# streams_v05.net
KiCad netlist of a schematic drawn in EAGLE
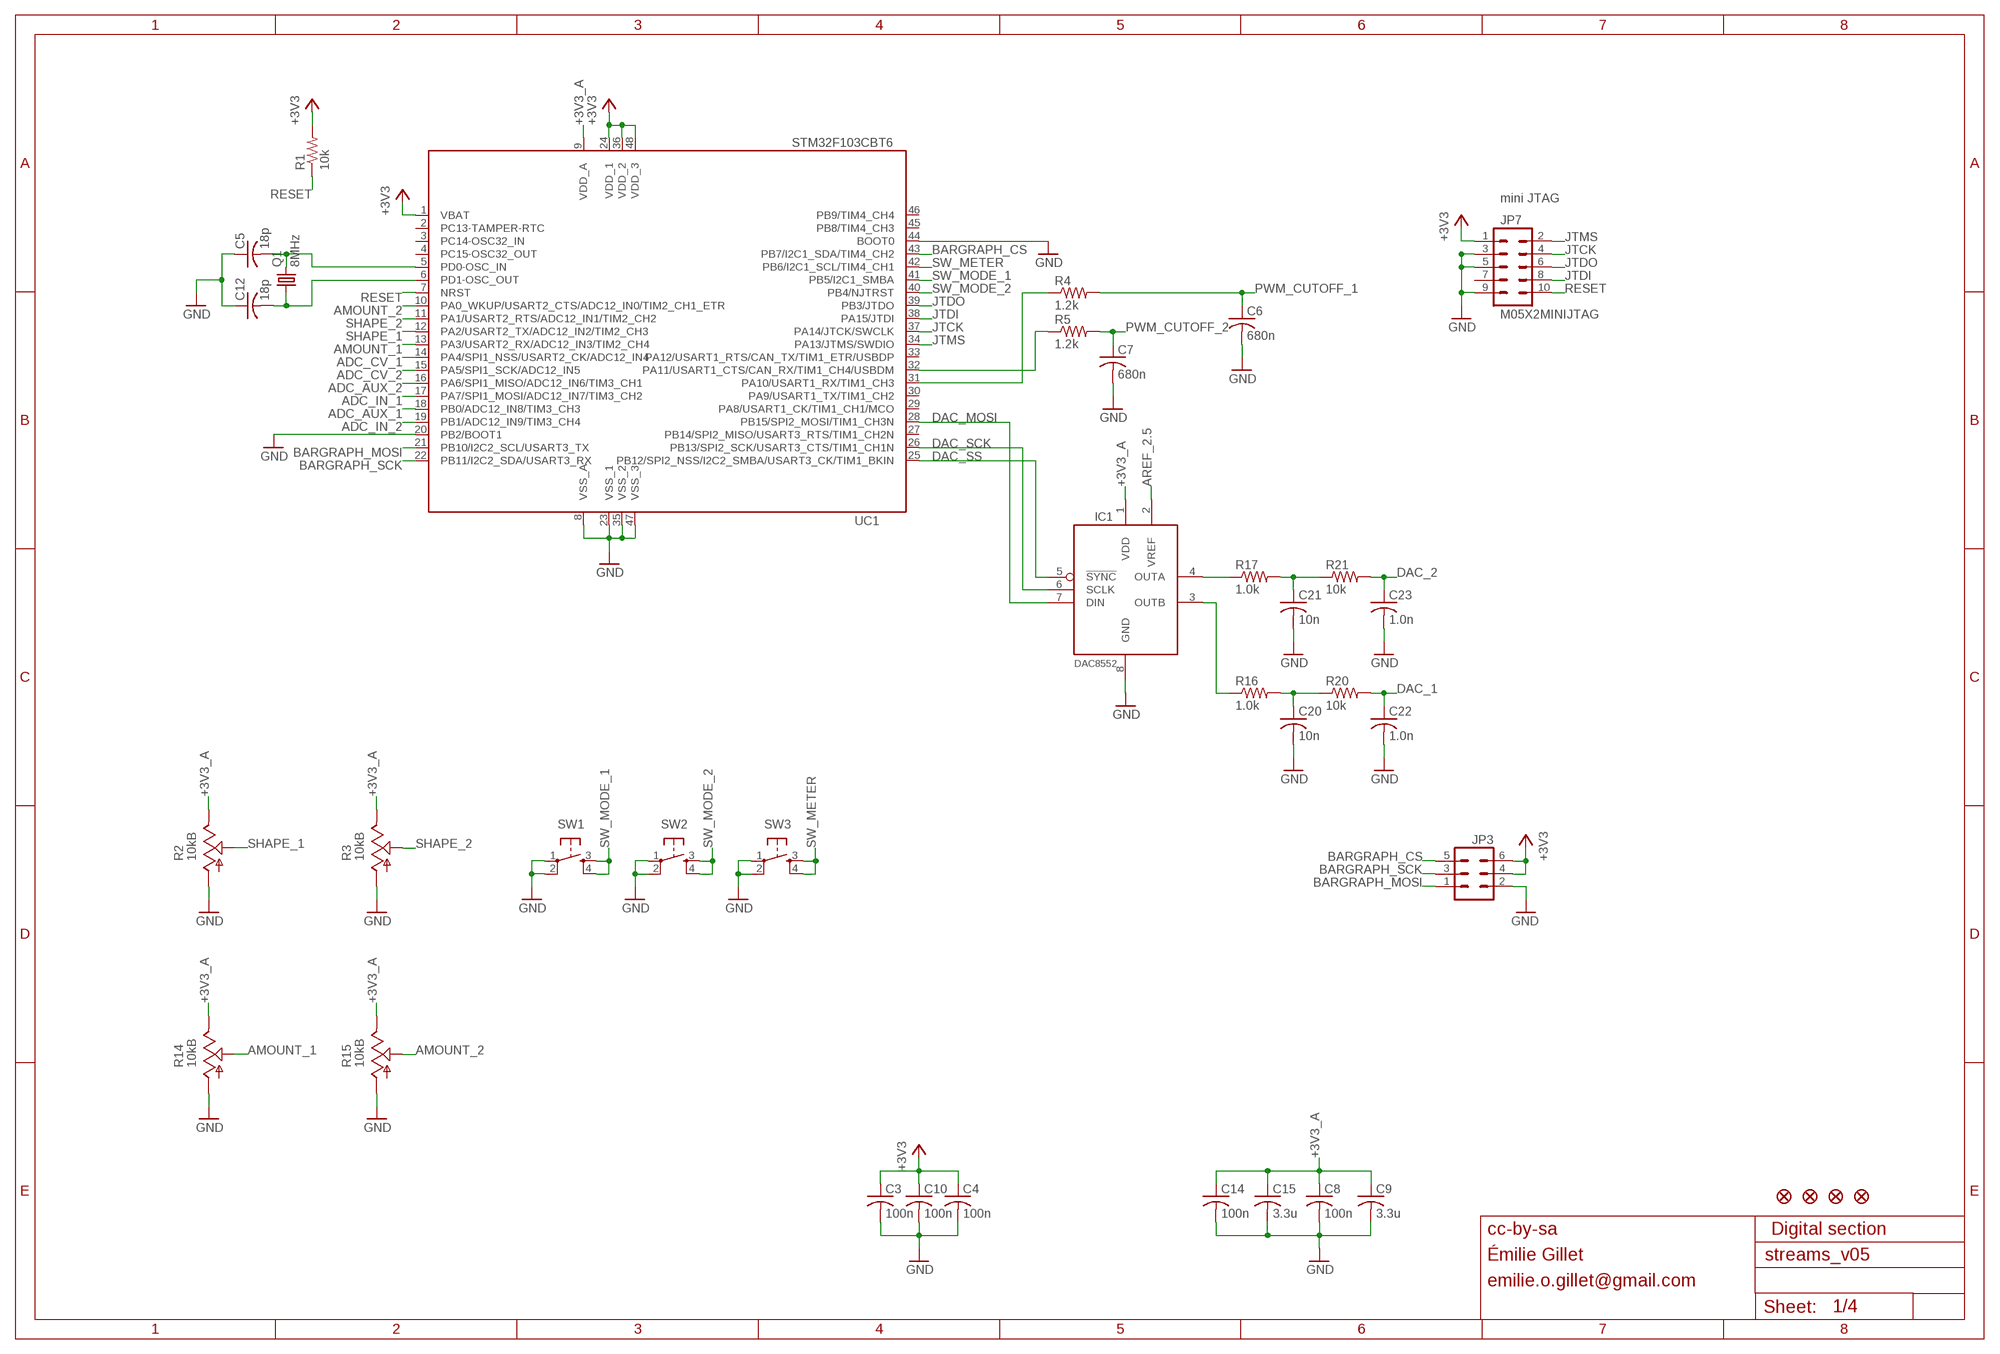
[diagram p0: schematic, sheet 1]
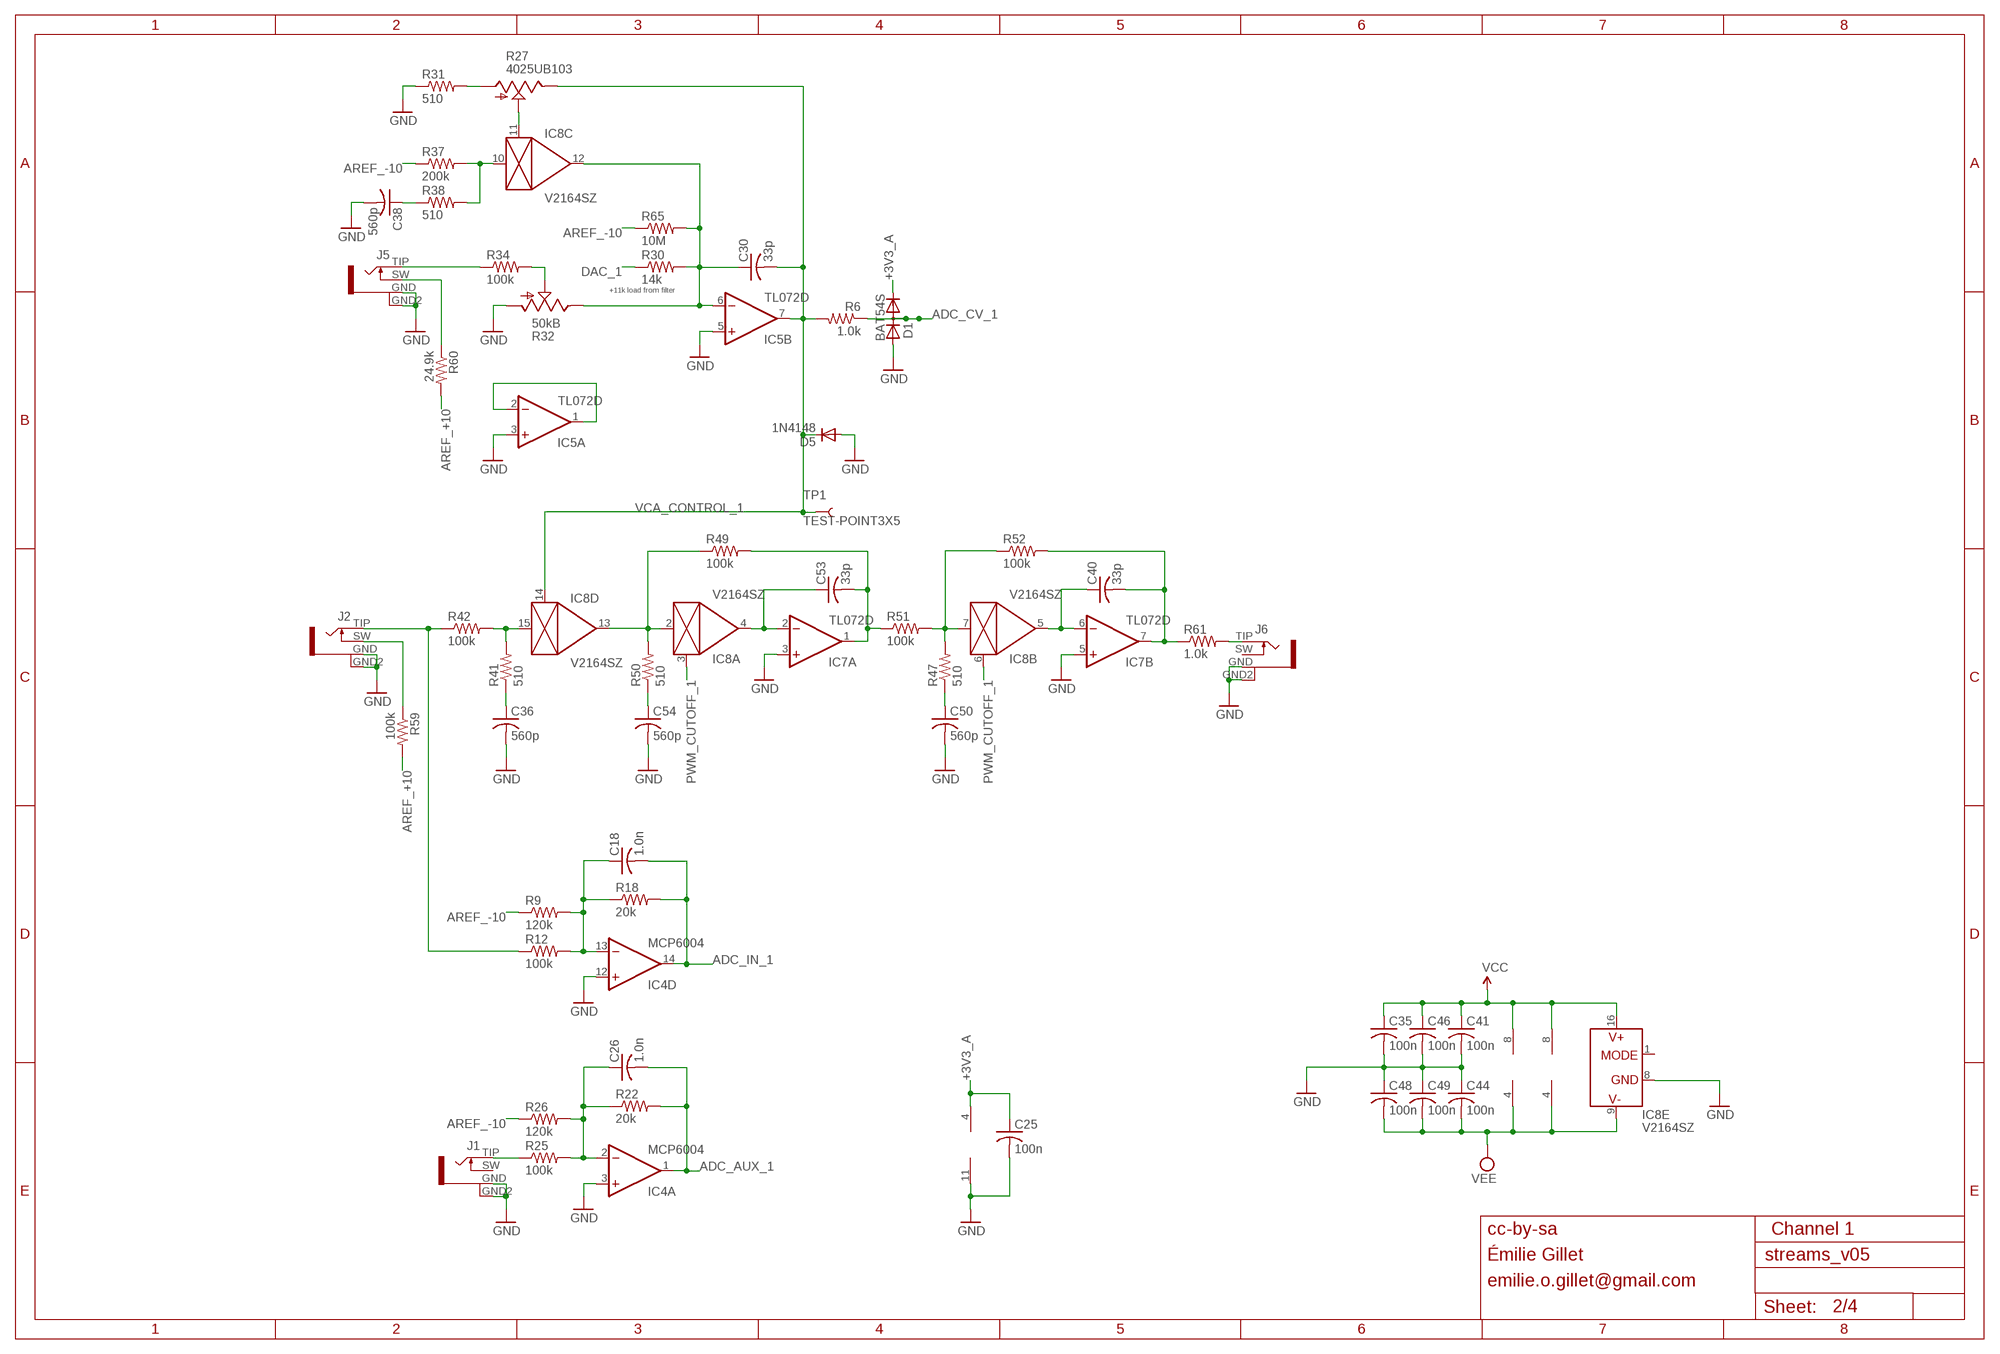
[diagram p1: schematic, sheet 2]
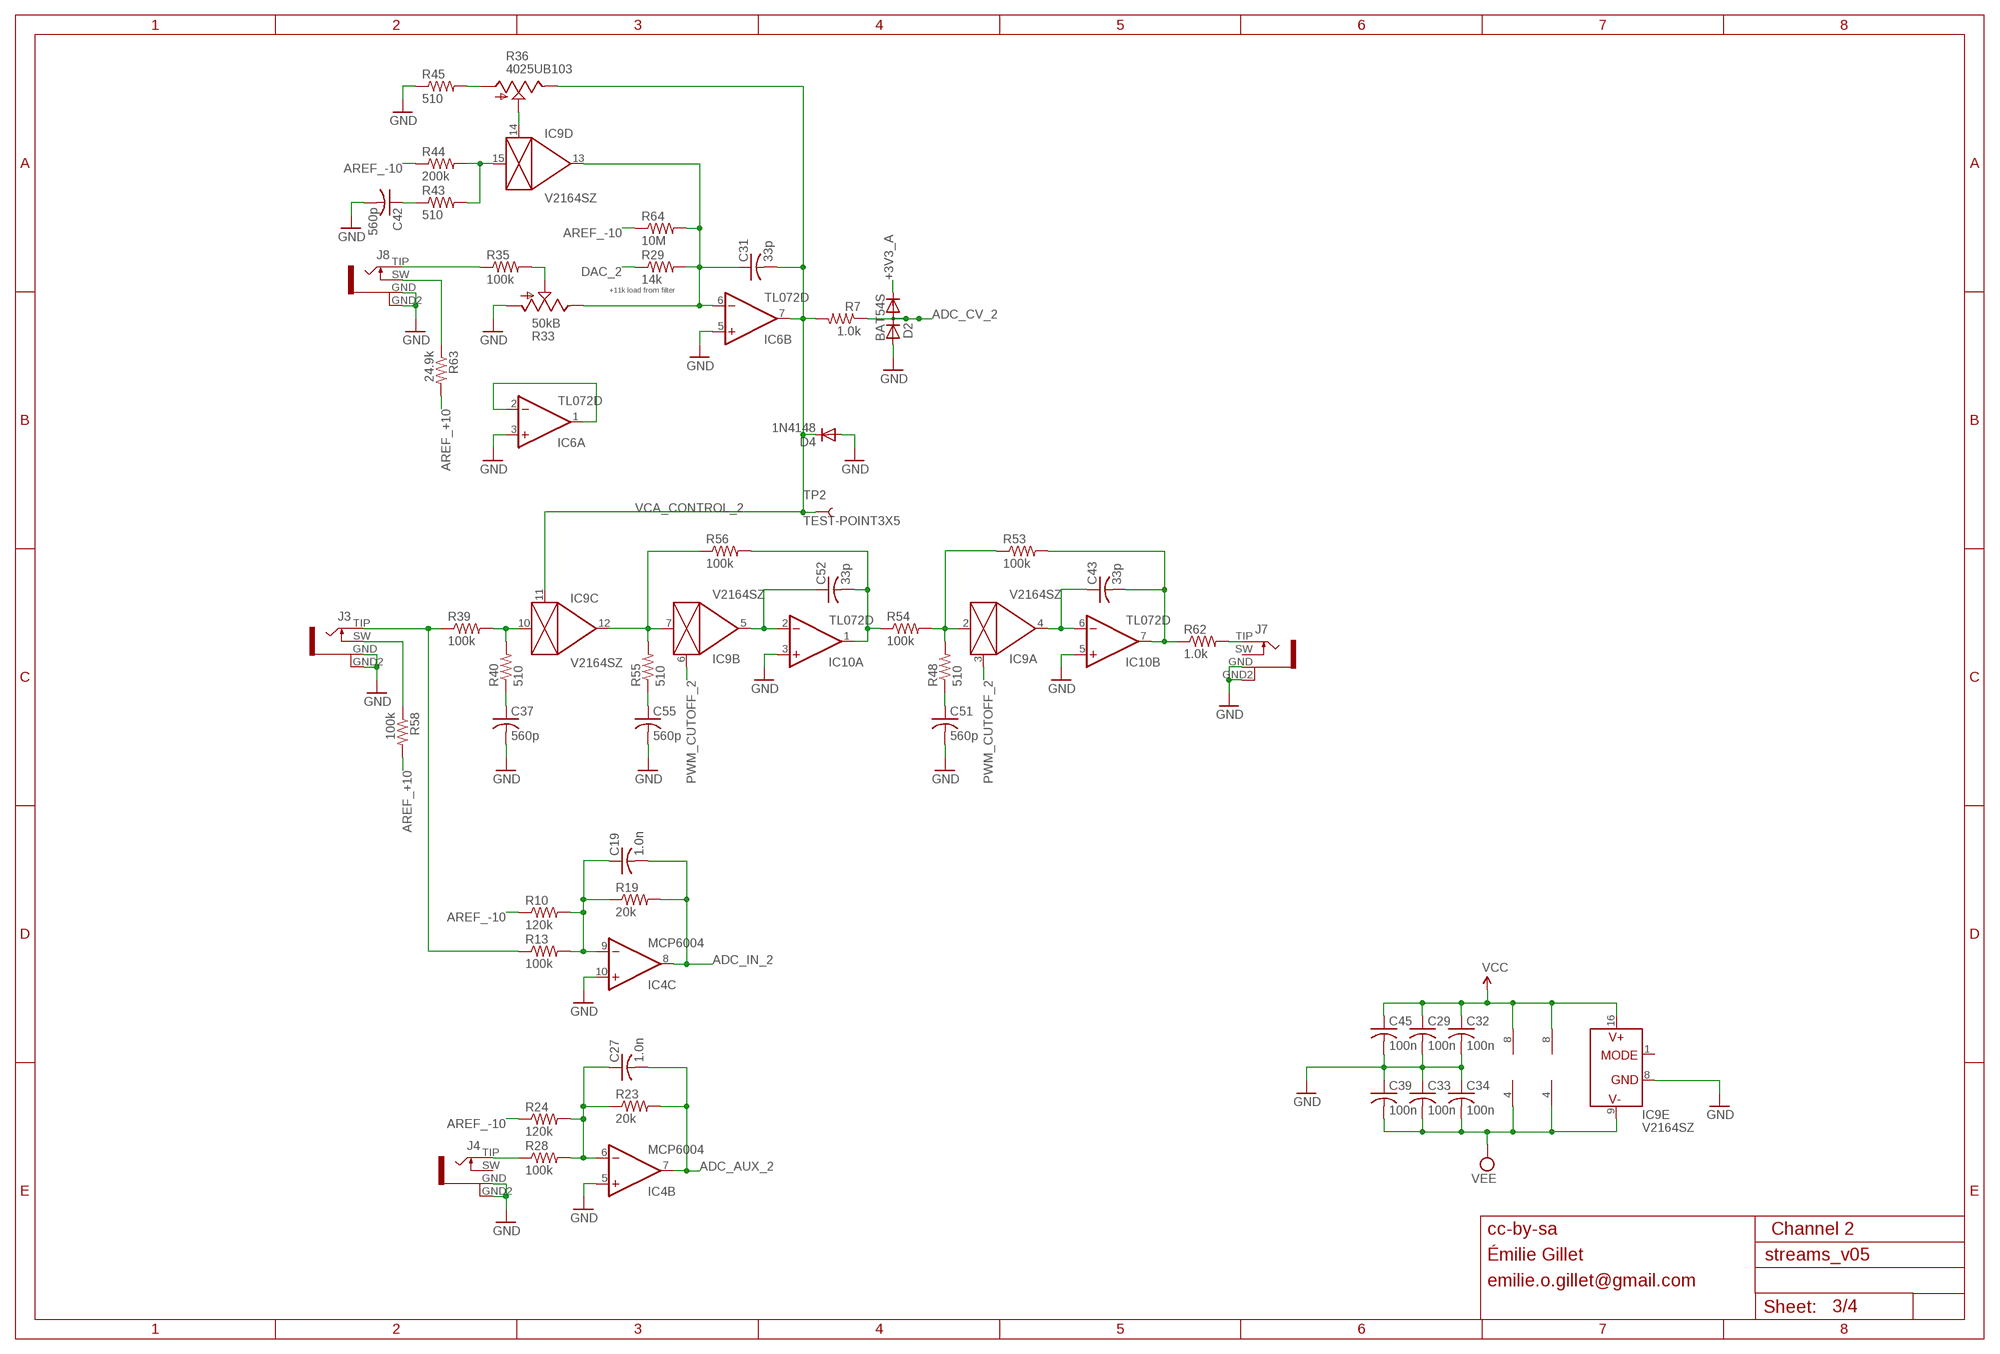
[diagram p2: schematic, sheet 3]
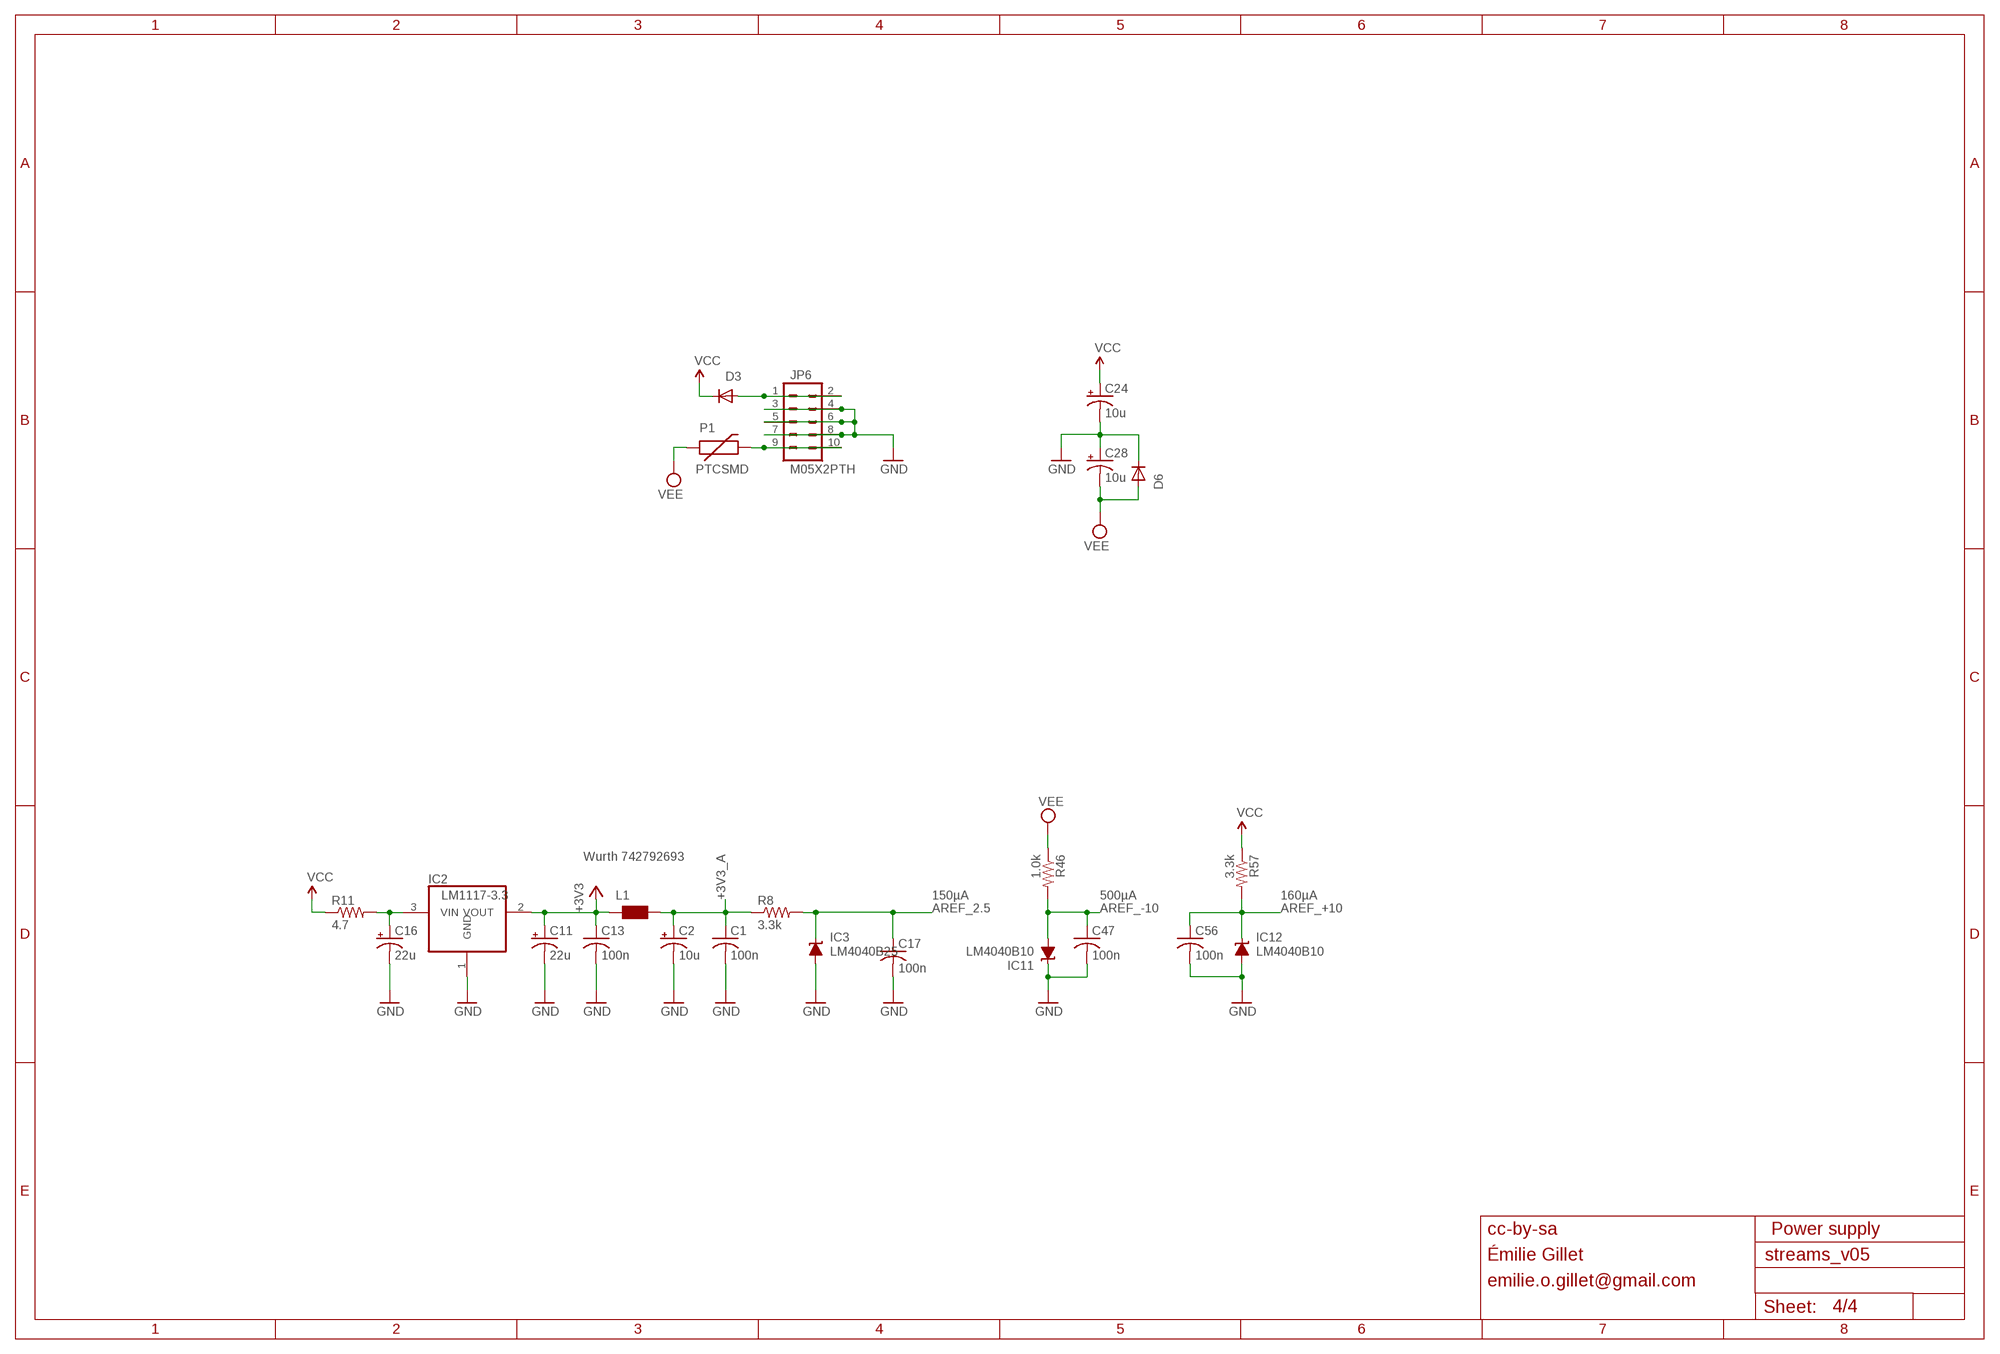
[diagram p3: schematic, sheet 4]

(export (version "E")
  (design (tool "Eeschema 10.0.6"))
  (components
    (comp (ref "C19")
      (value "1.0n")
      (footprint "eagle-import:C0603")
      (libsource (lib "eagle-import") (part "C-USC0603"))
    )
    (comp (ref "C27")
      (value "1.0n")
      (footprint "eagle-import:C0603")
      (libsource (lib "eagle-import") (part "C-USC0603"))
    )
    (comp (ref "C29")
      (value "100n")
      (footprint "eagle-import:C0603")
      (libsource (lib "eagle-import") (part "C-USC0603"))
    )
    (comp (ref "C31")
      (value "33p")
      (footprint "eagle-import:C0603")
      (libsource (lib "eagle-import") (part "C-USC0603"))
    )
    (comp (ref "C32")
      (value "100n")
      (footprint "eagle-import:C0603")
      (libsource (lib "eagle-import") (part "C-USC0603"))
    )
    (comp (ref "C33")
      (value "100n")
      (footprint "eagle-import:C0603")
      (libsource (lib "eagle-import") (part "C-USC0603"))
    )
    (comp (ref "C34")
      (value "100n")
      (footprint "eagle-import:C0603")
      (libsource (lib "eagle-import") (part "C-USC0603"))
    )
    (comp (ref "C37")
      (value "560p")
      (footprint "eagle-import:C0603")
      (libsource (lib "eagle-import") (part "C-USC0603"))
    )
    (comp (ref "C39")
      (value "100n")
      (footprint "eagle-import:C0603")
      (libsource (lib "eagle-import") (part "C-USC0603"))
    )
    (comp (ref "C42")
      (value "560p")
      (footprint "eagle-import:C0603")
      (libsource (lib "eagle-import") (part "C-USC0603"))
    )
    (comp (ref "C43")
      (value "33p")
      (footprint "eagle-import:C0603")
      (libsource (lib "eagle-import") (part "C-USC0603"))
    )
    (comp (ref "C45")
      (value "100n")
      (footprint "eagle-import:C0603")
      (libsource (lib "eagle-import") (part "C-USC0603"))
    )
    (comp (ref "C51")
      (value "560p")
      (footprint "eagle-import:C0603")
      (libsource (lib "eagle-import") (part "C-USC0603"))
    )
    (comp (ref "C52")
      (value "33p")
      (footprint "eagle-import:C0603")
      (libsource (lib "eagle-import") (part "C-USC0603"))
    )
    (comp (ref "C55")
      (value "560p")
      (footprint "eagle-import:C0603")
      (libsource (lib "eagle-import") (part "C-USC0603"))
    )
    (comp (ref "D2")
      (value "BAT54S")
      (footprint "eagle-import:SOT23")
      (libsource (lib "eagle-import") (part "DIODE_2CACA-SOT23"))
    )
    (comp (ref "D4")
      (value "1N4148")
      (footprint "eagle-import:SOD323-W")
      (libsource (lib "eagle-import") (part "DIODE-SOD323-W"))
    )
    (comp (ref "IC4")
      (value "MCP6004")
      (footprint "eagle-import:SO14")
      (libsource (lib "eagle-import") (part "TL074D"))
    )
    (comp (ref "IC6")
      (value "TL072D")
      (footprint "eagle-import:SO08")
      (libsource (lib "eagle-import") (part "TL072D"))
    )
    (comp (ref "IC9")
      (value "V2164SZ")
      (footprint "eagle-import:SOIC16N")
      (libsource (lib "eagle-import") (part "SSM2164S"))
    )
    (comp (ref "IC10")
      (value "TL072D")
      (footprint "eagle-import:SO08")
      (libsource (lib "eagle-import") (part "TL072D"))
    )
    (comp (ref "J3")
      (value "PJ301WQP")
      (footprint "eagle-import:WQP_PJ_301BM_WIDER")
      (libsource (lib "eagle-import") (part "PJ301WQP"))
    )
    (comp (ref "J4")
      (value "PJ301WQP")
      (footprint "eagle-import:WQP_PJ_301BM_WIDER")
      (libsource (lib "eagle-import") (part "PJ301WQP"))
    )
    (comp (ref "J7")
      (value "PJ301WQP")
      (footprint "eagle-import:WQP_PJ_301BM_WIDER")
      (libsource (lib "eagle-import") (part "PJ301WQP"))
    )
    (comp (ref "J8")
      (value "PJ301WQP")
      (footprint "eagle-import:WQP_PJ_301BM_WIDER")
      (libsource (lib "eagle-import") (part "PJ301WQP"))
    )
    (comp (ref "R7")
      (value "1.0k")
      (footprint "eagle-import:R0603")
      (libsource (lib "eagle-import") (part "R-US_R0603"))
    )
    (comp (ref "R10")
      (value "120k")
      (footprint "eagle-import:R0603")
      (libsource (lib "eagle-import") (part "R-US_R0603"))
    )
    (comp (ref "R13")
      (value "100k")
      (footprint "eagle-import:R0603")
      (libsource (lib "eagle-import") (part "R-US_R0603"))
    )
    (comp (ref "R19")
      (value "20k")
      (footprint "eagle-import:R0603")
      (libsource (lib "eagle-import") (part "R-US_R0603"))
    )
    (comp (ref "R23")
      (value "20k")
      (footprint "eagle-import:R0603")
      (libsource (lib "eagle-import") (part "R-US_R0603"))
    )
    (comp (ref "R24")
      (value "120k")
      (footprint "eagle-import:R0603")
      (libsource (lib "eagle-import") (part "R-US_R0603"))
    )
    (comp (ref "R28")
      (value "100k")
      (footprint "eagle-import:R0603")
      (libsource (lib "eagle-import") (part "R-US_R0603"))
    )
    (comp (ref "R29")
      (value "14k")
      (footprint "eagle-import:R0603")
      (libsource (lib "eagle-import") (part "R-US_R0603"))
    )
    (comp (ref "R33")
      (value "50kB")
      (footprint "eagle-import:ALPS_POT_VERTICAL_PS")
      (libsource (lib "eagle-import") (part "POT_USVERTICAL_PS"))
    )
    (comp (ref "R35")
      (value "100k")
      (footprint "eagle-import:R0603")
      (libsource (lib "eagle-import") (part "R-US_R0603"))
    )
    (comp (ref "R36")
      (value "4025UB103")
      (footprint "eagle-import:ALPS_POT_VERTICAL")
      (libsource (lib "eagle-import") (part "POT_USVERTICAL"))
    )
    (comp (ref "R39")
      (value "100k")
      (footprint "eagle-import:R0603")
      (libsource (lib "eagle-import") (part "R-US_R0603"))
    )
    (comp (ref "R40")
      (value "510")
      (footprint "eagle-import:R0603")
      (libsource (lib "eagle-import") (part "R-US_R0603"))
    )
    (comp (ref "R43")
      (value "510")
      (footprint "eagle-import:R0603")
      (libsource (lib "eagle-import") (part "R-US_R0603"))
    )
    (comp (ref "R44")
      (value "200k")
      (footprint "eagle-import:R0603")
      (libsource (lib "eagle-import") (part "R-US_R0603"))
    )
    (comp (ref "R45")
      (value "510")
      (footprint "eagle-import:R0603")
      (libsource (lib "eagle-import") (part "R-US_R0603"))
    )
    (comp (ref "R48")
      (value "510")
      (footprint "eagle-import:R0603")
      (libsource (lib "eagle-import") (part "R-US_R0603"))
    )
    (comp (ref "R53")
      (value "100k")
      (footprint "eagle-import:R0603")
      (libsource (lib "eagle-import") (part "R-US_R0603"))
    )
    (comp (ref "R54")
      (value "100k")
      (footprint "eagle-import:R0603")
      (libsource (lib "eagle-import") (part "R-US_R0603"))
    )
    (comp (ref "R55")
      (value "510")
      (footprint "eagle-import:R0603")
      (libsource (lib "eagle-import") (part "R-US_R0603"))
    )
    (comp (ref "R56")
      (value "100k")
      (footprint "eagle-import:R0603")
      (libsource (lib "eagle-import") (part "R-US_R0603"))
    )
    (comp (ref "R58")
      (value "100k")
      (footprint "eagle-import:R0603")
      (libsource (lib "eagle-import") (part "R-US_R0603"))
    )
    (comp (ref "R62")
      (value "1.0k")
      (footprint "eagle-import:R0603")
      (libsource (lib "eagle-import") (part "R-US_R0603"))
    )
    (comp (ref "R63")
      (value "24.9k")
      (footprint "eagle-import:R0603")
      (libsource (lib "eagle-import") (part "R-US_R0603"))
    )
    (comp (ref "R64")
      (value "10M")
      (footprint "eagle-import:R0603")
      (libsource (lib "eagle-import") (part "R-US_R0603"))
    )
    (comp (ref "TP2")
      (value "TEST-POINT3X5")
      (footprint "eagle-import:PAD.03X.05")
      (libsource (lib "eagle-import") (part "TEST-POINT3X5"))
    )
    (comp (ref "C18")
      (value "1.0n")
      (footprint "eagle-import:C0603")
      (libsource (lib "eagle-import") (part "C-USC0603"))
    )
    (comp (ref "C25")
      (value "100n")
      (footprint "eagle-import:C0603")
      (libsource (lib "eagle-import") (part "C-USC0603"))
    )
    (comp (ref "C26")
      (value "1.0n")
      (footprint "eagle-import:C0603")
      (libsource (lib "eagle-import") (part "C-USC0603"))
    )
    (comp (ref "C30")
      (value "33p")
      (footprint "eagle-import:C0603")
      (libsource (lib "eagle-import") (part "C-USC0603"))
    )
    (comp (ref "C35")
      (value "100n")
      (footprint "eagle-import:C0603")
      (libsource (lib "eagle-import") (part "C-USC0603"))
    )
    (comp (ref "C36")
      (value "560p")
      (footprint "eagle-import:C0603")
      (libsource (lib "eagle-import") (part "C-USC0603"))
    )
    (comp (ref "C38")
      (value "560p")
      (footprint "eagle-import:C0603")
      (libsource (lib "eagle-import") (part "C-USC0603"))
    )
    (comp (ref "C40")
      (value "33p")
      (footprint "eagle-import:C0603")
      (libsource (lib "eagle-import") (part "C-USC0603"))
    )
    (comp (ref "C41")
      (value "100n")
      (footprint "eagle-import:C0603")
      (libsource (lib "eagle-import") (part "C-USC0603"))
    )
    (comp (ref "C44")
      (value "100n")
      (footprint "eagle-import:C0603")
      (libsource (lib "eagle-import") (part "C-USC0603"))
    )
    (comp (ref "C46")
      (value "100n")
      (footprint "eagle-import:C0603")
      (libsource (lib "eagle-import") (part "C-USC0603"))
    )
    (comp (ref "C48")
      (value "100n")
      (footprint "eagle-import:C0603")
      (libsource (lib "eagle-import") (part "C-USC0603"))
    )
    (comp (ref "C49")
      (value "100n")
      (footprint "eagle-import:C0603")
      (libsource (lib "eagle-import") (part "C-USC0603"))
    )
    (comp (ref "C50")
      (value "560p")
      (footprint "eagle-import:C0603")
      (libsource (lib "eagle-import") (part "C-USC0603"))
    )
    (comp (ref "C53")
      (value "33p")
      (footprint "eagle-import:C0603")
      (libsource (lib "eagle-import") (part "C-USC0603"))
    )
    (comp (ref "C54")
      (value "560p")
      (footprint "eagle-import:C0603")
      (libsource (lib "eagle-import") (part "C-USC0603"))
    )
    (comp (ref "D1")
      (value "BAT54S")
      (footprint "eagle-import:SOT23")
      (libsource (lib "eagle-import") (part "DIODE_2CACA-SOT23"))
    )
    (comp (ref "D5")
      (value "1N4148")
      (footprint "eagle-import:SOD323-W")
      (libsource (lib "eagle-import") (part "DIODE-SOD323-W"))
    )
    (comp (ref "IC5")
      (value "TL072D")
      (footprint "eagle-import:SO08")
      (libsource (lib "eagle-import") (part "TL072D"))
    )
    (comp (ref "IC7")
      (value "TL072D")
      (footprint "eagle-import:SO08")
      (libsource (lib "eagle-import") (part "TL072D"))
    )
    (comp (ref "IC8")
      (value "V2164SZ")
      (footprint "eagle-import:SOIC16N")
      (libsource (lib "eagle-import") (part "SSM2164S"))
    )
    (comp (ref "J1")
      (value "PJ301WQP")
      (footprint "eagle-import:WQP_PJ_301BM_WIDER")
      (libsource (lib "eagle-import") (part "PJ301WQP"))
    )
    (comp (ref "J2")
      (value "PJ301WQP")
      (footprint "eagle-import:WQP_PJ_301BM_WIDER")
      (libsource (lib "eagle-import") (part "PJ301WQP"))
    )
    (comp (ref "J5")
      (value "PJ301WQP")
      (footprint "eagle-import:WQP_PJ_301BM_WIDER")
      (libsource (lib "eagle-import") (part "PJ301WQP"))
    )
    (comp (ref "J6")
      (value "PJ301WQP")
      (footprint "eagle-import:WQP_PJ_301BM_WIDER")
      (libsource (lib "eagle-import") (part "PJ301WQP"))
    )
    (comp (ref "R6")
      (value "1.0k")
      (footprint "eagle-import:R0603")
      (libsource (lib "eagle-import") (part "R-US_R0603"))
    )
    (comp (ref "R9")
      (value "120k")
      (footprint "eagle-import:R0603")
      (libsource (lib "eagle-import") (part "R-US_R0603"))
    )
    (comp (ref "R12")
      (value "100k")
      (footprint "eagle-import:R0603")
      (libsource (lib "eagle-import") (part "R-US_R0603"))
    )
    (comp (ref "R18")
      (value "20k")
      (footprint "eagle-import:R0603")
      (libsource (lib "eagle-import") (part "R-US_R0603"))
    )
    (comp (ref "R22")
      (value "20k")
      (footprint "eagle-import:R0603")
      (libsource (lib "eagle-import") (part "R-US_R0603"))
    )
    (comp (ref "R25")
      (value "100k")
      (footprint "eagle-import:R0603")
      (libsource (lib "eagle-import") (part "R-US_R0603"))
    )
    (comp (ref "R26")
      (value "120k")
      (footprint "eagle-import:R0603")
      (libsource (lib "eagle-import") (part "R-US_R0603"))
    )
    (comp (ref "R27")
      (value "4025UB103")
      (footprint "eagle-import:ALPS_POT_VERTICAL")
      (libsource (lib "eagle-import") (part "POT_USVERTICAL"))
    )
    (comp (ref "R30")
      (value "14k")
      (footprint "eagle-import:R0603")
      (libsource (lib "eagle-import") (part "R-US_R0603"))
    )
    (comp (ref "R31")
      (value "510")
      (footprint "eagle-import:R0603")
      (libsource (lib "eagle-import") (part "R-US_R0603"))
    )
    (comp (ref "R32")
      (value "50kB")
      (footprint "eagle-import:ALPS_POT_VERTICAL_PS")
      (libsource (lib "eagle-import") (part "POT_USVERTICAL_PS"))
    )
    (comp (ref "R34")
      (value "100k")
      (footprint "eagle-import:R0603")
      (libsource (lib "eagle-import") (part "R-US_R0603"))
    )
    (comp (ref "R37")
      (value "200k")
      (footprint "eagle-import:R0603")
      (libsource (lib "eagle-import") (part "R-US_R0603"))
    )
    (comp (ref "R38")
      (value "510")
      (footprint "eagle-import:R0603")
      (libsource (lib "eagle-import") (part "R-US_R0603"))
    )
    (comp (ref "R41")
      (value "510")
      (footprint "eagle-import:R0603")
      (libsource (lib "eagle-import") (part "R-US_R0603"))
    )
    (comp (ref "R42")
      (value "100k")
      (footprint "eagle-import:R0603")
      (libsource (lib "eagle-import") (part "R-US_R0603"))
    )
    (comp (ref "R47")
      (value "510")
      (footprint "eagle-import:R0603")
      (libsource (lib "eagle-import") (part "R-US_R0603"))
    )
    (comp (ref "R49")
      (value "100k")
      (footprint "eagle-import:R0603")
      (libsource (lib "eagle-import") (part "R-US_R0603"))
    )
    (comp (ref "R50")
      (value "510")
      (footprint "eagle-import:R0603")
      (libsource (lib "eagle-import") (part "R-US_R0603"))
    )
    (comp (ref "R51")
      (value "100k")
      (footprint "eagle-import:R0603")
      (libsource (lib "eagle-import") (part "R-US_R0603"))
    )
    (comp (ref "R52")
      (value "100k")
      (footprint "eagle-import:R0603")
      (libsource (lib "eagle-import") (part "R-US_R0603"))
    )
    (comp (ref "R59")
      (value "100k")
      (footprint "eagle-import:R0603")
      (libsource (lib "eagle-import") (part "R-US_R0603"))
    )
    (comp (ref "R60")
      (value "24.9k")
      (footprint "eagle-import:R0603")
      (libsource (lib "eagle-import") (part "R-US_R0603"))
    )
    (comp (ref "R61")
      (value "1.0k")
      (footprint "eagle-import:R0603")
      (libsource (lib "eagle-import") (part "R-US_R0603"))
    )
    (comp (ref "R65")
      (value "10M")
      (footprint "eagle-import:R0603")
      (libsource (lib "eagle-import") (part "R-US_R0603"))
    )
    (comp (ref "TP1")
      (value "TEST-POINT3X5")
      (footprint "eagle-import:PAD.03X.05")
      (libsource (lib "eagle-import") (part "TEST-POINT3X5"))
    )
    (comp (ref "C1")
      (value "100n")
      (footprint "eagle-import:C0603")
      (libsource (lib "eagle-import") (part "C-USC0603"))
    )
    (comp (ref "C2")
      (value "10u")
      (footprint "eagle-import:PANASONIC_B")
      (libsource (lib "eagle-import") (part "CPOL-USB"))
    )
    (comp (ref "C11")
      (value "22u")
      (footprint "eagle-import:PANASONIC_B")
      (libsource (lib "eagle-import") (part "CPOL-USB"))
    )
    (comp (ref "C13")
      (value "100n")
      (footprint "eagle-import:C0603")
      (libsource (lib "eagle-import") (part "C-USC0603"))
    )
    (comp (ref "C16")
      (value "22u")
      (footprint "eagle-import:PANASONIC_C")
      (libsource (lib "eagle-import") (part "CPOL-USC"))
    )
    (comp (ref "C17")
      (value "100n")
      (footprint "eagle-import:C0603")
      (libsource (lib "eagle-import") (part "C-USC0603"))
    )
    (comp (ref "C24")
      (value "10u")
      (footprint "eagle-import:PANASONIC_B")
      (libsource (lib "eagle-import") (part "CPOL-USB"))
    )
    (comp (ref "C28")
      (value "10u")
      (footprint "eagle-import:PANASONIC_B")
      (libsource (lib "eagle-import") (part "CPOL-USB"))
    )
    (comp (ref "C47")
      (value "100n")
      (footprint "eagle-import:C0603")
      (libsource (lib "eagle-import") (part "C-USC0603"))
    )
    (comp (ref "C56")
      (value "100n")
      (footprint "eagle-import:C0603")
      (libsource (lib "eagle-import") (part "C-USC0603"))
    )
    (comp (ref "D3")
      (value "1N5819HW")
      (footprint "eagle-import:SOD123")
      (libsource (lib "eagle-import") (part "DIODE-SOD123"))
    )
    (comp (ref "D6")
      (value "1N5819HW")
      (footprint "eagle-import:SOD123")
      (libsource (lib "eagle-import") (part "DIODE-SOD123"))
    )
    (comp (ref "IC2")
      (value "LM1117-3.3")
      (footprint "eagle-import:SOT223")
      (libsource (lib "eagle-import") (part "REG1117"))
    )
    (comp (ref "IC3")
      (value "LM4040B25")
      (footprint "eagle-import:DBZ_R-PDSO-G3")
      (libsource (lib "eagle-import") (part "LM4041DBZB12"))
    )
    (comp (ref "IC11")
      (value "LM4040B10")
      (footprint "eagle-import:DBZ_R-PDSO-G3")
      (libsource (lib "eagle-import") (part "LM4041DBZB12"))
    )
    (comp (ref "IC12")
      (value "LM4040B10")
      (footprint "eagle-import:DBZ_R-PDSO-G3")
      (libsource (lib "eagle-import") (part "LM4041DBZB12"))
    )
    (comp (ref "JP6")
      (value "M05X2PTH")
      (footprint "eagle-import:AVR_ICSP")
      (libsource (lib "eagle-import") (part "M05X2PTH"))
    )
    (comp (ref "L1")
      (value "WE-CBF_0603")
      (footprint "eagle-import:0603")
      (libsource (lib "eagle-import") (part "WE-CBF_0603"))
    )
    (comp (ref "P1")
      (value "PTCSMD")
      (footprint "eagle-import:PTC-1206")
      (libsource (lib "eagle-import") (part "PTCSMD"))
    )
    (comp (ref "R8")
      (value "3.3k")
      (footprint "eagle-import:R0603")
      (libsource (lib "eagle-import") (part "R-US_R0603"))
    )
    (comp (ref "R11")
      (value "4.7")
      (footprint "eagle-import:R1206")
      (libsource (lib "eagle-import") (part "R-US_R1206"))
    )
    (comp (ref "R46")
      (value "1.0k")
      (footprint "eagle-import:R0603")
      (libsource (lib "eagle-import") (part "R-US_R0603"))
    )
    (comp (ref "R57")
      (value "3.3k")
      (footprint "eagle-import:R0603")
      (libsource (lib "eagle-import") (part "R-US_R0603"))
    )
    (comp (ref "C3")
      (value "100n")
      (footprint "eagle-import:C0603")
      (libsource (lib "eagle-import") (part "C-USC0603"))
    )
    (comp (ref "C4")
      (value "100n")
      (footprint "eagle-import:C0603")
      (libsource (lib "eagle-import") (part "C-USC0603"))
    )
    (comp (ref "C5")
      (value "18p")
      (footprint "eagle-import:C0603")
      (libsource (lib "eagle-import") (part "C-USC0603"))
    )
    (comp (ref "C6")
      (value "680n")
      (footprint "eagle-import:C0603")
      (libsource (lib "eagle-import") (part "C-USC0603"))
    )
    (comp (ref "C7")
      (value "680n")
      (footprint "eagle-import:C0603")
      (libsource (lib "eagle-import") (part "C-USC0603"))
    )
    (comp (ref "C8")
      (value "100n")
      (footprint "eagle-import:C0603")
      (libsource (lib "eagle-import") (part "C-USC0603"))
    )
    (comp (ref "C9")
      (value "3.3u")
      (footprint "eagle-import:C0603")
      (libsource (lib "eagle-import") (part "C-USC0603"))
    )
    (comp (ref "C10")
      (value "100n")
      (footprint "eagle-import:C0603")
      (libsource (lib "eagle-import") (part "C-USC0603"))
    )
    (comp (ref "C12")
      (value "18p")
      (footprint "eagle-import:C0603")
      (libsource (lib "eagle-import") (part "C-USC0603"))
    )
    (comp (ref "C14")
      (value "100n")
      (footprint "eagle-import:C0603")
      (libsource (lib "eagle-import") (part "C-USC0603"))
    )
    (comp (ref "C15")
      (value "3.3u")
      (footprint "eagle-import:C0603")
      (libsource (lib "eagle-import") (part "C-USC0603"))
    )
    (comp (ref "C20")
      (value "10n")
      (footprint "eagle-import:C0603")
      (libsource (lib "eagle-import") (part "C-USC0603"))
    )
    (comp (ref "C21")
      (value "10n")
      (footprint "eagle-import:C0603")
      (libsource (lib "eagle-import") (part "C-USC0603"))
    )
    (comp (ref "C22")
      (value "1.0n")
      (footprint "eagle-import:C0603")
      (libsource (lib "eagle-import") (part "C-USC0603"))
    )
    (comp (ref "C23")
      (value "1.0n")
      (footprint "eagle-import:C0603")
      (libsource (lib "eagle-import") (part "C-USC0603"))
    )
    (comp (ref "IC1")
      (value "DAC8552")
      (footprint "eagle-import:MSOP-8")
      (libsource (lib "eagle-import") (part "DAC8552"))
    )
    (comp (ref "JP1")
      (value "FIDUCIAL1X2")
      (footprint "eagle-import:FIDUCIAL-1X2")
      (libsource (lib "eagle-import") (part "FIDUCIAL1X2"))
    )
    (comp (ref "JP2")
      (value "FIDUCIAL1X2")
      (footprint "eagle-import:FIDUCIAL-1X2")
      (libsource (lib "eagle-import") (part "FIDUCIAL1X2"))
    )
    (comp (ref "JP3")
      (value "M03X2BOTTOM")
      (footprint "eagle-import:2X3_BOTTOM")
      (libsource (lib "eagle-import") (part "M03X2BOTTOM"))
    )
    (comp (ref "JP4")
      (value "FIDUCIAL1X2")
      (footprint "eagle-import:FIDUCIAL-1X2")
      (libsource (lib "eagle-import") (part "FIDUCIAL1X2"))
    )
    (comp (ref "JP5")
      (value "FIDUCIAL1X2")
      (footprint "eagle-import:FIDUCIAL-1X2")
      (libsource (lib "eagle-import") (part "FIDUCIAL1X2"))
    )
    (comp (ref "JP7")
      (value "M05X2MINIJTAG")
      (footprint "eagle-import:2X5-1.27")
      (libsource (lib "eagle-import") (part "M05X2MINIJTAG"))
    )
    (comp (ref "Q1")
      (value "8MHz")
      (footprint "eagle-import:HC49UP")
      (libsource (lib "eagle-import") (part "CRYSTALHC49UP"))
    )
    (comp (ref "R1")
      (value "10k")
      (footprint "eagle-import:R0603")
      (libsource (lib "eagle-import") (part "R-US_R0603"))
    )
    (comp (ref "R2")
      (value "10kB")
      (footprint "eagle-import:ALPS_POT_VERTICAL_PS")
      (libsource (lib "eagle-import") (part "POT_USVERTICAL_PS"))
    )
    (comp (ref "R3")
      (value "10kB")
      (footprint "eagle-import:ALPS_POT_VERTICAL_PS")
      (libsource (lib "eagle-import") (part "POT_USVERTICAL_PS"))
    )
    (comp (ref "R4")
      (value "1.2k")
      (footprint "eagle-import:R0603")
      (libsource (lib "eagle-import") (part "R-US_R0603"))
    )
    (comp (ref "R5")
      (value "1.2k")
      (footprint "eagle-import:R0603")
      (libsource (lib "eagle-import") (part "R-US_R0603"))
    )
    (comp (ref "R14")
      (value "10kB")
      (footprint "eagle-import:ALPS_POT_VERTICAL_PS")
      (libsource (lib "eagle-import") (part "POT_USVERTICAL_PS"))
    )
    (comp (ref "R15")
      (value "10kB")
      (footprint "eagle-import:ALPS_POT_VERTICAL_PS")
      (libsource (lib "eagle-import") (part "POT_USVERTICAL_PS"))
    )
    (comp (ref "R16")
      (value "1.0k")
      (footprint "eagle-import:R0603")
      (libsource (lib "eagle-import") (part "R-US_R0603"))
    )
    (comp (ref "R17")
      (value "1.0k")
      (footprint "eagle-import:R0603")
      (libsource (lib "eagle-import") (part "R-US_R0603"))
    )
    (comp (ref "R20")
      (value "10k")
      (footprint "eagle-import:R0603")
      (libsource (lib "eagle-import") (part "R-US_R0603"))
    )
    (comp (ref "R21")
      (value "10k")
      (footprint "eagle-import:R0603")
      (libsource (lib "eagle-import") (part "R-US_R0603"))
    )
    (comp (ref "SW1")
      (value "TAC_SWITCHPTH")
      (footprint "eagle-import:TACTILE-PTH")
      (libsource (lib "eagle-import") (part "TAC_SWITCHPTH"))
    )
    (comp (ref "SW2")
      (value "TAC_SWITCHPTH")
      (footprint "eagle-import:TACTILE-PTH")
      (libsource (lib "eagle-import") (part "TAC_SWITCHPTH"))
    )
    (comp (ref "SW3")
      (value "TAC_SWITCHPTH")
      (footprint "eagle-import:TACTILE-PTH")
      (libsource (lib "eagle-import") (part "TAC_SWITCHPTH"))
    )
    (comp (ref "UC1")
      (value "STM32F103CBT6")
      (footprint "eagle-import:LQFP48")
      (libsource (lib "eagle-import") (part "STM32F103CB"))
    )
  )
  (nets
    (net (code "1") (name "+3V3") (class "Default")
      (node (ref "C10") (pin "1") (pinfunction "1_1") (pintype "passive"))
      (node (ref "C11") (pin "+") (pinfunction "+_+") (pintype "passive"))
      (node (ref "C13") (pin "1") (pinfunction "1_1") (pintype "passive"))
      (node (ref "C3") (pin "1") (pinfunction "1_1") (pintype "passive"))
      (node (ref "C4") (pin "1") (pinfunction "1_1") (pintype "passive"))
      (node (ref "IC2") (pin "2") (pinfunction "VOUT_2") (pintype "output"))
      (node (ref "JP3") (pin "4") (pinfunction "4_4") (pintype "passive"))
      (node (ref "JP3") (pin "6") (pinfunction "6_6") (pintype "passive"))
      (node (ref "JP7") (pin "1") (pinfunction "1_1") (pintype "passive"))
      (node (ref "L1") (pin "1") (pinfunction "1_1") (pintype "passive"))
      (node (ref "R1") (pin "2") (pinfunction "2_2") (pintype "passive"))
      (node (ref "UC1") (pin "1") (pinfunction "VBAT_1") (pintype "power_in"))
      (node (ref "UC1") (pin "24") (pinfunction "VDD_1_24") (pintype "power_in"))
      (node (ref "UC1") (pin "36") (pinfunction "VDD_2_36") (pintype "power_in"))
      (node (ref "UC1") (pin "48") (pinfunction "VDD_3_48") (pintype "power_in"))
    )
    (net (code "2") (name "+3V3_A") (class "Default")
      (node (ref "C1") (pin "1") (pinfunction "1_1") (pintype "passive"))
      (node (ref "C14") (pin "1") (pinfunction "1_1") (pintype "passive"))
      (node (ref "C15") (pin "1") (pinfunction "1_1") (pintype "passive"))
      (node (ref "C2") (pin "+") (pinfunction "+_+") (pintype "passive"))
      (node (ref "C25") (pin "1") (pinfunction "1_1") (pintype "passive"))
      (node (ref "C8") (pin "1") (pinfunction "1_1") (pintype "passive"))
      (node (ref "C9") (pin "1") (pinfunction "1_1") (pintype "passive"))
      (node (ref "D1") (pin "2") (pinfunction "C_2") (pintype "passive"))
      (node (ref "D2") (pin "2") (pinfunction "C_2") (pintype "passive"))
      (node (ref "IC1") (pin "1") (pinfunction "VDD_1") (pintype "power_in"))
      (node (ref "IC4") (pin "4") (pinfunction "V+_4") (pintype "power_in"))
      (node (ref "L1") (pin "2") (pinfunction "2_2") (pintype "passive"))
      (node (ref "R14") (pin "P$1") (pinfunction "E_P$1") (pintype "passive"))
      (node (ref "R15") (pin "P$1") (pinfunction "E_P$1") (pintype "passive"))
      (node (ref "R2") (pin "P$1") (pinfunction "E_P$1") (pintype "passive"))
      (node (ref "R3") (pin "P$1") (pinfunction "E_P$1") (pintype "passive"))
      (node (ref "R8") (pin "1") (pinfunction "1_1") (pintype "passive"))
      (node (ref "UC1") (pin "9") (pinfunction "VDD_A_9") (pintype "power_in"))
    )
    (net (code "3") (name "ADC_AUX_1") (class "Default")
      (node (ref "C26") (pin "2") (pinfunction "2_2") (pintype "passive"))
      (node (ref "IC4") (pin "1") (pinfunction "OUT_1") (pintype "output"))
      (node (ref "R22") (pin "2") (pinfunction "2_2") (pintype "passive"))
      (node (ref "UC1") (pin "18") (pinfunction "PB0/ADC12_IN8/TIM3_CH3_18") (pintype "bidirectional"))
    )
    (net (code "4") (name "ADC_AUX_2") (class "Default")
      (node (ref "C27") (pin "2") (pinfunction "2_2") (pintype "passive"))
      (node (ref "IC4") (pin "7") (pinfunction "OUT_7") (pintype "output"))
      (node (ref "R23") (pin "2") (pinfunction "2_2") (pintype "passive"))
      (node (ref "UC1") (pin "16") (pinfunction "PA6/SPI1_MISO/ADC12_IN6/TIM3_CH1_16") (pintype "bidirectional"))
    )
    (net (code "5") (name "ADC_CV_1") (class "Default")
      (node (ref "D1") (pin "3") (pinfunction "AC_3") (pintype "passive"))
      (node (ref "R6") (pin "1") (pinfunction "1_1") (pintype "passive"))
      (node (ref "UC1") (pin "14") (pinfunction "PA4/SPI1_NSS/USART2_CK/ADC12_IN4_14") (pintype "bidirectional"))
    )
    (net (code "6") (name "ADC_CV_2") (class "Default")
      (node (ref "D2") (pin "3") (pinfunction "AC_3") (pintype "passive"))
      (node (ref "R7") (pin "1") (pinfunction "1_1") (pintype "passive"))
      (node (ref "UC1") (pin "15") (pinfunction "PA5/SPI1_SCK/ADC12_IN5_15") (pintype "bidirectional"))
    )
    (net (code "7") (name "ADC_IN_1") (class "Default")
      (node (ref "C18") (pin "2") (pinfunction "2_2") (pintype "passive"))
      (node (ref "IC4") (pin "14") (pinfunction "OUT_14") (pintype "output"))
      (node (ref "R18") (pin "2") (pinfunction "2_2") (pintype "passive"))
      (node (ref "UC1") (pin "17") (pinfunction "PA7/SPI1_MOSI/ADC12_IN7/TIM3_CH2_17") (pintype "bidirectional"))
    )
    (net (code "8") (name "ADC_IN_2") (class "Default")
      (node (ref "C19") (pin "2") (pinfunction "2_2") (pintype "passive"))
      (node (ref "IC4") (pin "8") (pinfunction "OUT_8") (pintype "output"))
      (node (ref "R19") (pin "2") (pinfunction "2_2") (pintype "passive"))
      (node (ref "UC1") (pin "19") (pinfunction "PB1/ADC12_IN9/TIM3_CH4_19") (pintype "bidirectional"))
    )
    (net (code "9") (name "AMOUNT_1") (class "Default")
      (node (ref "R14") (pin "P$2") (pinfunction "S_P$2") (pintype "passive"))
      (node (ref "UC1") (pin "13") (pinfunction "PA3/USART2_RX/ADC12_IN3/TIM2_CH4_13") (pintype "bidirectional"))
    )
    (net (code "10") (name "AMOUNT_2") (class "Default")
      (node (ref "R15") (pin "P$2") (pinfunction "S_P$2") (pintype "passive"))
      (node (ref "UC1") (pin "10") (pinfunction "PA0_WKUP/USART2_CTS/ADC12_IN0/TIM2_CH1_ETR_10") (pintype "bidirectional"))
    )
    (net (code "11") (name "AREF_+10") (class "Default")
      (node (ref "C56") (pin "1") (pinfunction "1_1") (pintype "passive"))
      (node (ref "IC12") (pin "1") (pinfunction "C_1") (pintype "passive"))
      (node (ref "R57") (pin "2") (pinfunction "2_2") (pintype "passive"))
      (node (ref "R58") (pin "2") (pinfunction "2_2") (pintype "passive"))
      (node (ref "R59") (pin "2") (pinfunction "2_2") (pintype "passive"))
      (node (ref "R60") (pin "2") (pinfunction "2_2") (pintype "passive"))
      (node (ref "R63") (pin "2") (pinfunction "2_2") (pintype "passive"))
    )
    (net (code "12") (name "AREF_-10") (class "Default")
      (node (ref "C47") (pin "1") (pinfunction "1_1") (pintype "passive"))
      (node (ref "IC11") (pin "2") (pinfunction "A_2") (pintype "passive"))
      (node (ref "R10") (pin "1") (pinfunction "1_1") (pintype "passive"))
      (node (ref "R24") (pin "1") (pinfunction "1_1") (pintype "passive"))
      (node (ref "R26") (pin "1") (pinfunction "1_1") (pintype "passive"))
      (node (ref "R37") (pin "1") (pinfunction "1_1") (pintype "passive"))
      (node (ref "R44") (pin "1") (pinfunction "1_1") (pintype "passive"))
      (node (ref "R46") (pin "2") (pinfunction "2_2") (pintype "passive"))
      (node (ref "R64") (pin "1") (pinfunction "1_1") (pintype "passive"))
      (node (ref "R65") (pin "1") (pinfunction "1_1") (pintype "passive"))
      (node (ref "R9") (pin "1") (pinfunction "1_1") (pintype "passive"))
    )
    (net (code "13") (name "AREF_2.5") (class "Default")
      (node (ref "C17") (pin "1") (pinfunction "1_1") (pintype "passive"))
      (node (ref "IC1") (pin "2") (pinfunction "VREF_2") (pintype "power_in"))
      (node (ref "IC3") (pin "1") (pinfunction "C_1") (pintype "passive"))
      (node (ref "R8") (pin "2") (pinfunction "2_2") (pintype "passive"))
    )
    (net (code "14") (name "BARGRAPH_CS") (class "Default")
      (node (ref "JP3") (pin "5") (pinfunction "5_5") (pintype "passive"))
      (node (ref "UC1") (pin "43") (pinfunction "PB7/I2C1_SDA/TIM4_CH2_43") (pintype "bidirectional"))
    )
    (net (code "15") (name "BARGRAPH_MOSI") (class "Default")
      (node (ref "JP3") (pin "1") (pinfunction "1_1") (pintype "passive"))
      (node (ref "UC1") (pin "21") (pinfunction "PB10/I2C2_SCL/USART3_TX_21") (pintype "input"))
    )
    (net (code "16") (name "BARGRAPH_SCK") (class "Default")
      (node (ref "JP3") (pin "3") (pinfunction "3_3") (pintype "passive"))
      (node (ref "UC1") (pin "22") (pinfunction "PB11/I2C2_SDA/USART3_RX_22") (pintype "input"))
    )
    (net (code "17") (name "DAC_1") (class "Default")
      (node (ref "C22") (pin "1") (pinfunction "1_1") (pintype "passive"))
      (node (ref "R20") (pin "2") (pinfunction "2_2") (pintype "passive"))
      (node (ref "R30") (pin "1") (pinfunction "1_1") (pintype "passive"))
    )
    (net (code "18") (name "DAC_2") (class "Default")
      (node (ref "C23") (pin "1") (pinfunction "1_1") (pintype "passive"))
      (node (ref "R21") (pin "2") (pinfunction "2_2") (pintype "passive"))
      (node (ref "R29") (pin "1") (pinfunction "1_1") (pintype "passive"))
    )
    (net (code "19") (name "DAC_MOSI") (class "Default")
      (node (ref "IC1") (pin "7") (pinfunction "DIN_7") (pintype "bidirectional"))
      (node (ref "UC1") (pin "28") (pinfunction "PB15/SPI2_MOSI/TIM1_CH3N_28") (pintype "input"))
    )
    (net (code "20") (name "DAC_SCK") (class "Default")
      (node (ref "IC1") (pin "6") (pinfunction "SCLK_6") (pintype "bidirectional"))
      (node (ref "UC1") (pin "26") (pinfunction "PB13/SPI2_SCK/USART3_CTS/TIM1_CH1N_26") (pintype "input"))
    )
    (net (code "21") (name "DAC_SS") (class "Default")
      (node (ref "IC1") (pin "5") (pinfunction "~{SYNC}_5") (pintype "bidirectional"))
      (node (ref "UC1") (pin "25") (pinfunction "PB12/SPI2_NSS/I2C2_SMBA/USART3_CK/TIM1_BKIN_25") (pintype "input"))
    )
    (net (code "22") (name "GND") (class "Default")
      (node (ref "C1") (pin "2") (pinfunction "2_2") (pintype "passive"))
      (node (ref "C10") (pin "2") (pinfunction "2_2") (pintype "passive"))
      (node (ref "C11") (pin "-") (pinfunction "-_-") (pintype "passive"))
      (node (ref "C12") (pin "1") (pinfunction "1_1") (pintype "passive"))
      (node (ref "C13") (pin "2") (pinfunction "2_2") (pintype "passive"))
      (node (ref "C14") (pin "2") (pinfunction "2_2") (pintype "passive"))
      (node (ref "C15") (pin "2") (pinfunction "2_2") (pintype "passive"))
      (node (ref "C16") (pin "-") (pinfunction "-_-") (pintype "passive"))
      (node (ref "C17") (pin "2") (pinfunction "2_2") (pintype "passive"))
      (node (ref "C2") (pin "-") (pinfunction "-_-") (pintype "passive"))
      (node (ref "C20") (pin "2") (pinfunction "2_2") (pintype "passive"))
      (node (ref "C21") (pin "2") (pinfunction "2_2") (pintype "passive"))
      (node (ref "C22") (pin "2") (pinfunction "2_2") (pintype "passive"))
      (node (ref "C23") (pin "2") (pinfunction "2_2") (pintype "passive"))
      (node (ref "C24") (pin "-") (pinfunction "-_-") (pintype "passive"))
      (node (ref "C25") (pin "2") (pinfunction "2_2") (pintype "passive"))
      (node (ref "C28") (pin "+") (pinfunction "+_+") (pintype "passive"))
      (node (ref "C29") (pin "2") (pinfunction "2_2") (pintype "passive"))
      (node (ref "C3") (pin "2") (pinfunction "2_2") (pintype "passive"))
      (node (ref "C32") (pin "2") (pinfunction "2_2") (pintype "passive"))
      (node (ref "C33") (pin "1") (pinfunction "1_1") (pintype "passive"))
      (node (ref "C34") (pin "1") (pinfunction "1_1") (pintype "passive"))
      (node (ref "C35") (pin "2") (pinfunction "2_2") (pintype "passive"))
      (node (ref "C36") (pin "2") (pinfunction "2_2") (pintype "passive"))
      (node (ref "C37") (pin "2") (pinfunction "2_2") (pintype "passive"))
      (node (ref "C38") (pin "2") (pinfunction "2_2") (pintype "passive"))
      (node (ref "C39") (pin "1") (pinfunction "1_1") (pintype "passive"))
      (node (ref "C4") (pin "2") (pinfunction "2_2") (pintype "passive"))
      (node (ref "C41") (pin "2") (pinfunction "2_2") (pintype "passive"))
      (node (ref "C42") (pin "2") (pinfunction "2_2") (pintype "passive"))
      (node (ref "C44") (pin "1") (pinfunction "1_1") (pintype "passive"))
      (node (ref "C45") (pin "2") (pinfunction "2_2") (pintype "passive"))
      (node (ref "C46") (pin "2") (pinfunction "2_2") (pintype "passive"))
      (node (ref "C47") (pin "2") (pinfunction "2_2") (pintype "passive"))
      (node (ref "C48") (pin "1") (pinfunction "1_1") (pintype "passive"))
      (node (ref "C49") (pin "1") (pinfunction "1_1") (pintype "passive"))
      (node (ref "C5") (pin "1") (pinfunction "1_1") (pintype "passive"))
      (node (ref "C50") (pin "2") (pinfunction "2_2") (pintype "passive"))
      (node (ref "C51") (pin "2") (pinfunction "2_2") (pintype "passive"))
      (node (ref "C54") (pin "2") (pinfunction "2_2") (pintype "passive"))
      (node (ref "C55") (pin "2") (pinfunction "2_2") (pintype "passive"))
      (node (ref "C56") (pin "2") (pinfunction "2_2") (pintype "passive"))
      (node (ref "C6") (pin "2") (pinfunction "2_2") (pintype "passive"))
      (node (ref "C7") (pin "2") (pinfunction "2_2") (pintype "passive"))
      (node (ref "C8") (pin "2") (pinfunction "2_2") (pintype "passive"))
      (node (ref "C9") (pin "2") (pinfunction "2_2") (pintype "passive"))
      (node (ref "D1") (pin "1") (pinfunction "A_1") (pintype "passive"))
      (node (ref "D2") (pin "1") (pinfunction "A_1") (pintype "passive"))
      (node (ref "D4") (pin "A") (pinfunction "A_A") (pintype "passive"))
      (node (ref "D5") (pin "A") (pinfunction "A_A") (pintype "passive"))
      (node (ref "D6") (pin "C") (pinfunction "C_C") (pintype "passive"))
      (node (ref "IC1") (pin "8") (pinfunction "GND_8") (pintype "power_in"))
      (node (ref "IC10") (pin "3") (pinfunction "+IN_3") (pintype "input"))
      (node (ref "IC10") (pin "5") (pinfunction "+IN_5") (pintype "input"))
      (node (ref "IC11") (pin "1") (pinfunction "C_1") (pintype "passive"))
      (node (ref "IC12") (pin "2") (pinfunction "A_2") (pintype "passive"))
      (node (ref "IC2") (pin "1") (pinfunction "GND_1") (pintype "power_in"))
      (node (ref "IC3") (pin "2") (pinfunction "A_2") (pintype "passive"))
      (node (ref "IC4") (pin "10") (pinfunction "+IN_10") (pintype "input"))
      (node (ref "IC4") (pin "11") (pinfunction "V-_11") (pintype "power_in"))
      (node (ref "IC4") (pin "12") (pinfunction "+IN_12") (pintype "input"))
      (node (ref "IC4") (pin "3") (pinfunction "+IN_3") (pintype "input"))
      (node (ref "IC4") (pin "5") (pinfunction "+IN_5") (pintype "input"))
      (node (ref "IC5") (pin "3") (pinfunction "+IN_3") (pintype "input"))
      (node (ref "IC5") (pin "5") (pinfunction "+IN_5") (pintype "input"))
      (node (ref "IC6") (pin "3") (pinfunction "+IN_3") (pintype "input"))
      (node (ref "IC6") (pin "5") (pinfunction "+IN_5") (pintype "input"))
      (node (ref "IC7") (pin "3") (pinfunction "+IN_3") (pintype "input"))
      (node (ref "IC7") (pin "5") (pinfunction "+IN_5") (pintype "input"))
      (node (ref "IC8") (pin "8") (pinfunction "GND_8") (pintype "power_in"))
      (node (ref "IC9") (pin "8") (pinfunction "GND_8") (pintype "power_in"))
      (node (ref "J1") (pin "GND") (pinfunction "1_GND") (pintype "passive"))
      (node (ref "J1") (pin "GND2") (pinfunction "4_GND2") (pintype "passive"))
      (node (ref "J2") (pin "GND") (pinfunction "1_GND") (pintype "passive"))
      (node (ref "J2") (pin "GND2") (pinfunction "4_GND2") (pintype "passive"))
      (node (ref "J3") (pin "GND") (pinfunction "1_GND") (pintype "passive"))
      (node (ref "J3") (pin "GND2") (pinfunction "4_GND2") (pintype "passive"))
      (node (ref "J4") (pin "GND") (pinfunction "1_GND") (pintype "passive"))
      (node (ref "J4") (pin "GND2") (pinfunction "4_GND2") (pintype "passive"))
      (node (ref "J5") (pin "GND") (pinfunction "1_GND") (pintype "passive"))
      (node (ref "J5") (pin "GND2") (pinfunction "4_GND2") (pintype "passive"))
      (node (ref "J6") (pin "GND") (pinfunction "1_GND") (pintype "passive"))
      (node (ref "J6") (pin "GND2") (pinfunction "4_GND2") (pintype "passive"))
      (node (ref "J7") (pin "GND") (pinfunction "1_GND") (pintype "passive"))
      (node (ref "J7") (pin "GND2") (pinfunction "4_GND2") (pintype "passive"))
      (node (ref "J8") (pin "GND") (pinfunction "1_GND") (pintype "passive"))
      (node (ref "J8") (pin "GND2") (pinfunction "4_GND2") (pintype "passive"))
      (node (ref "JP3") (pin "2") (pinfunction "2_2") (pintype "passive"))
      (node (ref "JP6") (pin "3") (pinfunction "3_3") (pintype "passive"))
      (node (ref "JP6") (pin "4") (pinfunction "4_4") (pintype "passive"))
      (node (ref "JP6") (pin "5") (pinfunction "5_5") (pintype "passive"))
      (node (ref "JP6") (pin "6") (pinfunction "6_6") (pintype "passive"))
      (node (ref "JP6") (pin "7") (pinfunction "7_7") (pintype "passive"))
      (node (ref "JP6") (pin "8") (pinfunction "8_8") (pintype "passive"))
      (node (ref "JP7") (pin "3") (pinfunction "3_3") (pintype "passive"))
      (node (ref "JP7") (pin "5") (pinfunction "5_5") (pintype "passive"))
      (node (ref "JP7") (pin "9") (pinfunction "9_9") (pintype "passive"))
      (node (ref "R14") (pin "P$3") (pinfunction "A_P$3") (pintype "passive"))
      (node (ref "R15") (pin "P$3") (pinfunction "A_P$3") (pintype "passive"))
      (node (ref "R2") (pin "P$3") (pinfunction "A_P$3") (pintype "passive"))
      (node (ref "R3") (pin "P$3") (pinfunction "A_P$3") (pintype "passive"))
      (node (ref "R31") (pin "1") (pinfunction "1_1") (pintype "passive"))
      (node (ref "R32") (pin "P$3") (pinfunction "A_P$3") (pintype "passive"))
      (node (ref "R33") (pin "P$3") (pinfunction "A_P$3") (pintype "passive"))
      (node (ref "R45") (pin "1") (pinfunction "1_1") (pintype "passive"))
      (node (ref "SW1") (pin "1") (pinfunction "1_1") (pintype "passive"))
      (node (ref "SW1") (pin "2") (pinfunction "2_2") (pintype "passive"))
      (node (ref "SW2") (pin "1") (pinfunction "1_1") (pintype "passive"))
      (node (ref "SW2") (pin "2") (pinfunction "2_2") (pintype "passive"))
      (node (ref "SW3") (pin "1") (pinfunction "1_1") (pintype "passive"))
      (node (ref "SW3") (pin "2") (pinfunction "2_2") (pintype "passive"))
      (node (ref "UC1") (pin "20") (pinfunction "PB2/BOOT1_20") (pintype "bidirectional"))
      (node (ref "UC1") (pin "23") (pinfunction "VSS_1_23") (pintype "power_in"))
      (node (ref "UC1") (pin "35") (pinfunction "VSS_2_35") (pintype "power_in"))
      (node (ref "UC1") (pin "44") (pinfunction "BOOT0_44") (pintype "input"))
      (node (ref "UC1") (pin "47") (pinfunction "VSS_3_47") (pintype "power_in"))
      (node (ref "UC1") (pin "8") (pinfunction "VSS_A_8") (pintype "power_in"))
    )
    (net (code "23") (name "JTCK") (class "Default")
      (node (ref "JP7") (pin "4") (pinfunction "4_4") (pintype "passive"))
      (node (ref "UC1") (pin "37") (pinfunction "PA14/JTCK/SWCLK_37") (pintype "bidirectional"))
    )
    (net (code "24") (name "JTDI") (class "Default")
      (node (ref "JP7") (pin "8") (pinfunction "8_8") (pintype "passive"))
      (node (ref "UC1") (pin "38") (pinfunction "PA15/JTDI_38") (pintype "bidirectional"))
    )
    (net (code "25") (name "JTDO") (class "Default")
      (node (ref "JP7") (pin "6") (pinfunction "6_6") (pintype "passive"))
      (node (ref "UC1") (pin "39") (pinfunction "PB3/JTDO_39") (pintype "bidirectional"))
    )
    (net (code "26") (name "JTMS") (class "Default")
      (node (ref "JP7") (pin "2") (pinfunction "2_2") (pintype "passive"))
      (node (ref "UC1") (pin "34") (pinfunction "PA13/JTMS/SWDIO_34") (pintype "bidirectional"))
    )
    (net (code "27") (name "Net-(C20-Pad1)") (class "Default")
      (node (ref "C20") (pin "1") (pinfunction "1_1") (pintype "passive"))
      (node (ref "R16") (pin "2") (pinfunction "2_2") (pintype "passive"))
      (node (ref "R20") (pin "1") (pinfunction "1_1") (pintype "passive"))
    )
    (net (code "28") (name "Net-(C21-Pad1)") (class "Default")
      (node (ref "C21") (pin "1") (pinfunction "1_1") (pintype "passive"))
      (node (ref "R17") (pin "2") (pinfunction "2_2") (pintype "passive"))
      (node (ref "R21") (pin "1") (pinfunction "1_1") (pintype "passive"))
    )
    (net (code "29") (name "Net-(C36-Pad1)") (class "Default")
      (node (ref "C36") (pin "1") (pinfunction "1_1") (pintype "passive"))
      (node (ref "R41") (pin "1") (pinfunction "1_1") (pintype "passive"))
    )
    (net (code "30") (name "Net-(C37-Pad1)") (class "Default")
      (node (ref "C37") (pin "1") (pinfunction "1_1") (pintype "passive"))
      (node (ref "R40") (pin "1") (pinfunction "1_1") (pintype "passive"))
    )
    (net (code "31") (name "Net-(C38-Pad1)") (class "Default")
      (node (ref "C38") (pin "1") (pinfunction "1_1") (pintype "passive"))
      (node (ref "R38") (pin "1") (pinfunction "1_1") (pintype "passive"))
    )
    (net (code "32") (name "Net-(C42-Pad1)") (class "Default")
      (node (ref "C42") (pin "1") (pinfunction "1_1") (pintype "passive"))
      (node (ref "R43") (pin "1") (pinfunction "1_1") (pintype "passive"))
    )
    (net (code "33") (name "Net-(C50-Pad1)") (class "Default")
      (node (ref "C50") (pin "1") (pinfunction "1_1") (pintype "passive"))
      (node (ref "R47") (pin "1") (pinfunction "1_1") (pintype "passive"))
    )
    (net (code "34") (name "Net-(C51-Pad1)") (class "Default")
      (node (ref "C51") (pin "1") (pinfunction "1_1") (pintype "passive"))
      (node (ref "R48") (pin "1") (pinfunction "1_1") (pintype "passive"))
    )
    (net (code "35") (name "Net-(C54-Pad1)") (class "Default")
      (node (ref "C54") (pin "1") (pinfunction "1_1") (pintype "passive"))
      (node (ref "R50") (pin "1") (pinfunction "1_1") (pintype "passive"))
    )
    (net (code "36") (name "Net-(C55-Pad1)") (class "Default")
      (node (ref "C55") (pin "1") (pinfunction "1_1") (pintype "passive"))
      (node (ref "R55") (pin "1") (pinfunction "1_1") (pintype "passive"))
    )
    (net (code "37") (name "Net-(D3-PadA)") (class "Default")
      (node (ref "D3") (pin "A") (pinfunction "A_A") (pintype "passive"))
      (node (ref "JP6") (pin "1") (pinfunction "1_1") (pintype "passive"))
      (node (ref "JP6") (pin "2") (pinfunction "2_2") (pintype "passive"))
    )
    (net (code "38") (name "Net-(IC1-OUTA)") (class "Default")
      (node (ref "IC1") (pin "4") (pinfunction "OUTA_4") (pintype "output"))
      (node (ref "R17") (pin "1") (pinfunction "1_1") (pintype "passive"))
    )
    (net (code "39") (name "Net-(IC1-OUTB)") (class "Default")
      (node (ref "IC1") (pin "3") (pinfunction "OUTB_3") (pintype "input"))
      (node (ref "R16") (pin "1") (pinfunction "1_1") (pintype "passive"))
    )
    (net (code "40") (name "Net-(IC2-VIN)") (class "Default")
      (node (ref "C16") (pin "+") (pinfunction "+_+") (pintype "passive"))
      (node (ref "IC2") (pin "3") (pinfunction "VIN_3") (pintype "input"))
      (node (ref "R11") (pin "2") (pinfunction "2_2") (pintype "passive"))
    )
    (net (code "41") (name "Net-(IC4A--IN)") (class "Default")
      (node (ref "C26") (pin "1") (pinfunction "1_1") (pintype "passive"))
      (node (ref "IC4") (pin "2") (pinfunction "-IN_2") (pintype "input"))
      (node (ref "R22") (pin "1") (pinfunction "1_1") (pintype "passive"))
      (node (ref "R25") (pin "2") (pinfunction "2_2") (pintype "passive"))
      (node (ref "R26") (pin "2") (pinfunction "2_2") (pintype "passive"))
    )
    (net (code "42") (name "Net-(IC4B--IN)") (class "Default")
      (node (ref "C27") (pin "1") (pinfunction "1_1") (pintype "passive"))
      (node (ref "IC4") (pin "6") (pinfunction "-IN_6") (pintype "input"))
      (node (ref "R23") (pin "1") (pinfunction "1_1") (pintype "passive"))
      (node (ref "R24") (pin "2") (pinfunction "2_2") (pintype "passive"))
      (node (ref "R28") (pin "2") (pinfunction "2_2") (pintype "passive"))
    )
    (net (code "43") (name "Net-(IC4C--IN)") (class "Default")
      (node (ref "C19") (pin "1") (pinfunction "1_1") (pintype "passive"))
      (node (ref "IC4") (pin "9") (pinfunction "-IN_9") (pintype "input"))
      (node (ref "R10") (pin "2") (pinfunction "2_2") (pintype "passive"))
      (node (ref "R13") (pin "2") (pinfunction "2_2") (pintype "passive"))
      (node (ref "R19") (pin "1") (pinfunction "1_1") (pintype "passive"))
    )
    (net (code "44") (name "Net-(IC4D--IN)") (class "Default")
      (node (ref "C18") (pin "1") (pinfunction "1_1") (pintype "passive"))
      (node (ref "IC4") (pin "13") (pinfunction "-IN_13") (pintype "input"))
      (node (ref "R12") (pin "2") (pinfunction "2_2") (pintype "passive"))
      (node (ref "R18") (pin "1") (pinfunction "1_1") (pintype "passive"))
      (node (ref "R9") (pin "2") (pinfunction "2_2") (pintype "passive"))
    )
    (net (code "45") (name "Net-(IC5A--IN)") (class "Default")
      (node (ref "IC5") (pin "1") (pinfunction "OUT_1") (pintype "output"))
      (node (ref "IC5") (pin "2") (pinfunction "-IN_2") (pintype "input"))
    )
    (net (code "46") (name "Net-(IC5B--IN)") (class "Default")
      (node (ref "C30") (pin "1") (pinfunction "1_1") (pintype "passive"))
      (node (ref "IC5") (pin "6") (pinfunction "-IN_6") (pintype "input"))
      (node (ref "IC8") (pin "12") (pinfunction "OUT_12") (pintype "output"))
      (node (ref "R30") (pin "2") (pinfunction "2_2") (pintype "passive"))
      (node (ref "R32") (pin "P$1") (pinfunction "E_P$1") (pintype "passive"))
      (node (ref "R65") (pin "2") (pinfunction "2_2") (pintype "passive"))
    )
    (net (code "47") (name "Net-(IC6A--IN)") (class "Default")
      (node (ref "IC6") (pin "1") (pinfunction "OUT_1") (pintype "output"))
      (node (ref "IC6") (pin "2") (pinfunction "-IN_2") (pintype "input"))
    )
    (net (code "48") (name "Net-(IC6B--IN)") (class "Default")
      (node (ref "C31") (pin "1") (pinfunction "1_1") (pintype "passive"))
      (node (ref "IC6") (pin "6") (pinfunction "-IN_6") (pintype "input"))
      (node (ref "IC9") (pin "13") (pinfunction "OUT_13") (pintype "output"))
      (node (ref "R29") (pin "2") (pinfunction "2_2") (pintype "passive"))
      (node (ref "R33") (pin "P$1") (pinfunction "E_P$1") (pintype "passive"))
      (node (ref "R64") (pin "2") (pinfunction "2_2") (pintype "passive"))
    )
    (net (code "49") (name "Net-(IC7A--IN)") (class "Default")
      (node (ref "C53") (pin "1") (pinfunction "1_1") (pintype "passive"))
      (node (ref "IC7") (pin "2") (pinfunction "-IN_2") (pintype "input"))
      (node (ref "IC8") (pin "4") (pinfunction "OUT_4") (pintype "output"))
    )
    (net (code "50") (name "Net-(IC7A-OUT)") (class "Default")
      (node (ref "C53") (pin "2") (pinfunction "2_2") (pintype "passive"))
      (node (ref "IC7") (pin "1") (pinfunction "OUT_1") (pintype "output"))
      (node (ref "R49") (pin "2") (pinfunction "2_2") (pintype "passive"))
      (node (ref "R51") (pin "1") (pinfunction "1_1") (pintype "passive"))
    )
    (net (code "51") (name "Net-(IC7B--IN)") (class "Default")
      (node (ref "C40") (pin "1") (pinfunction "1_1") (pintype "passive"))
      (node (ref "IC7") (pin "6") (pinfunction "-IN_6") (pintype "input"))
      (node (ref "IC8") (pin "5") (pinfunction "OUT_5") (pintype "output"))
    )
    (net (code "52") (name "Net-(IC7B-OUT)") (class "Default")
      (node (ref "C40") (pin "2") (pinfunction "2_2") (pintype "passive"))
      (node (ref "IC7") (pin "7") (pinfunction "OUT_7") (pintype "output"))
      (node (ref "R52") (pin "2") (pinfunction "2_2") (pintype "passive"))
      (node (ref "R61") (pin "1") (pinfunction "1_1") (pintype "passive"))
    )
    (net (code "53") (name "Net-(IC8A-IN)") (class "Default")
      (node (ref "IC8") (pin "13") (pinfunction "OUT_13") (pintype "output"))
      (node (ref "IC8") (pin "2") (pinfunction "IN_2") (pintype "input"))
      (node (ref "R49") (pin "1") (pinfunction "1_1") (pintype "passive"))
      (node (ref "R50") (pin "2") (pinfunction "2_2") (pintype "passive"))
    )
    (net (code "54") (name "Net-(IC8B-IN)") (class "Default")
      (node (ref "IC8") (pin "7") (pinfunction "IN_7") (pintype "input"))
      (node (ref "R47") (pin "2") (pinfunction "2_2") (pintype "passive"))
      (node (ref "R51") (pin "2") (pinfunction "2_2") (pintype "passive"))
      (node (ref "R52") (pin "1") (pinfunction "1_1") (pintype "passive"))
    )
    (net (code "55") (name "Net-(IC8C-CTRL)") (class "Default")
      (node (ref "IC8") (pin "11") (pinfunction "CTRL_11") (pintype "input"))
      (node (ref "R27") (pin "P$2") (pinfunction "S_P$2") (pintype "passive"))
    )
    (net (code "56") (name "Net-(IC8C-IN)") (class "Default")
      (node (ref "IC8") (pin "10") (pinfunction "IN_10") (pintype "input"))
      (node (ref "R37") (pin "2") (pinfunction "2_2") (pintype "passive"))
      (node (ref "R38") (pin "2") (pinfunction "2_2") (pintype "passive"))
    )
    (net (code "57") (name "Net-(IC8D-IN)") (class "Default")
      (node (ref "IC8") (pin "15") (pinfunction "IN_15") (pintype "input"))
      (node (ref "R41") (pin "2") (pinfunction "2_2") (pintype "passive"))
      (node (ref "R42") (pin "2") (pinfunction "2_2") (pintype "passive"))
    )
    (net (code "58") (name "Net-(IC9A-IN)") (class "Default")
      (node (ref "IC9") (pin "2") (pinfunction "IN_2") (pintype "input"))
      (node (ref "R48") (pin "2") (pinfunction "2_2") (pintype "passive"))
      (node (ref "R53") (pin "1") (pinfunction "1_1") (pintype "passive"))
      (node (ref "R54") (pin "2") (pinfunction "2_2") (pintype "passive"))
    )
    (net (code "59") (name "Net-(IC9B-IN)") (class "Default")
      (node (ref "IC9") (pin "12") (pinfunction "OUT_12") (pintype "output"))
      (node (ref "IC9") (pin "7") (pinfunction "IN_7") (pintype "input"))
      (node (ref "R55") (pin "2") (pinfunction "2_2") (pintype "passive"))
      (node (ref "R56") (pin "1") (pinfunction "1_1") (pintype "passive"))
    )
    (net (code "60") (name "Net-(IC9C-IN)") (class "Default")
      (node (ref "IC9") (pin "10") (pinfunction "IN_10") (pintype "input"))
      (node (ref "R39") (pin "2") (pinfunction "2_2") (pintype "passive"))
      (node (ref "R40") (pin "2") (pinfunction "2_2") (pintype "passive"))
    )
    (net (code "61") (name "Net-(IC9D-CTRL)") (class "Default")
      (node (ref "IC9") (pin "14") (pinfunction "CTRL_14") (pintype "input"))
      (node (ref "R36") (pin "P$2") (pinfunction "S_P$2") (pintype "passive"))
    )
    (net (code "62") (name "Net-(IC9D-IN)") (class "Default")
      (node (ref "IC9") (pin "15") (pinfunction "IN_15") (pintype "input"))
      (node (ref "R43") (pin "2") (pinfunction "2_2") (pintype "passive"))
      (node (ref "R44") (pin "2") (pinfunction "2_2") (pintype "passive"))
    )
    (net (code "63") (name "Net-(IC10A--IN)") (class "Default")
      (node (ref "C52") (pin "1") (pinfunction "1_1") (pintype "passive"))
      (node (ref "IC10") (pin "2") (pinfunction "-IN_2") (pintype "input"))
      (node (ref "IC9") (pin "5") (pinfunction "OUT_5") (pintype "output"))
    )
    (net (code "64") (name "Net-(IC10A-OUT)") (class "Default")
      (node (ref "C52") (pin "2") (pinfunction "2_2") (pintype "passive"))
      (node (ref "IC10") (pin "1") (pinfunction "OUT_1") (pintype "output"))
      (node (ref "R54") (pin "1") (pinfunction "1_1") (pintype "passive"))
      (node (ref "R56") (pin "2") (pinfunction "2_2") (pintype "passive"))
    )
    (net (code "65") (name "Net-(IC10B--IN)") (class "Default")
      (node (ref "C43") (pin "1") (pinfunction "1_1") (pintype "passive"))
      (node (ref "IC10") (pin "6") (pinfunction "-IN_6") (pintype "input"))
      (node (ref "IC9") (pin "4") (pinfunction "OUT_4") (pintype "output"))
    )
    (net (code "66") (name "Net-(IC10B-OUT)") (class "Default")
      (node (ref "C43") (pin "2") (pinfunction "2_2") (pintype "passive"))
      (node (ref "IC10") (pin "7") (pinfunction "OUT_7") (pintype "output"))
      (node (ref "R53") (pin "2") (pinfunction "2_2") (pintype "passive"))
      (node (ref "R62") (pin "1") (pinfunction "1_1") (pintype "passive"))
    )
    (net (code "67") (name "Net-(J1-2)") (class "Default")
      (node (ref "J1") (pin "TIP") (pinfunction "2_TIP") (pintype "passive"))
      (node (ref "R25") (pin "1") (pinfunction "1_1") (pintype "passive"))
    )
    (net (code "68") (name "Net-(J2-2)") (class "Default")
      (node (ref "J2") (pin "TIP") (pinfunction "2_TIP") (pintype "passive"))
      (node (ref "R12") (pin "1") (pinfunction "1_1") (pintype "passive"))
      (node (ref "R42") (pin "1") (pinfunction "1_1") (pintype "passive"))
    )
    (net (code "69") (name "Net-(J2-3)") (class "Default")
      (node (ref "J2") (pin "SW") (pinfunction "3_SW") (pintype "passive"))
      (node (ref "R59") (pin "1") (pinfunction "1_1") (pintype "passive"))
    )
    (net (code "70") (name "Net-(J3-2)") (class "Default")
      (node (ref "J3") (pin "TIP") (pinfunction "2_TIP") (pintype "passive"))
      (node (ref "R13") (pin "1") (pinfunction "1_1") (pintype "passive"))
      (node (ref "R39") (pin "1") (pinfunction "1_1") (pintype "passive"))
    )
    (net (code "71") (name "Net-(J3-3)") (class "Default")
      (node (ref "J3") (pin "SW") (pinfunction "3_SW") (pintype "passive"))
      (node (ref "R58") (pin "1") (pinfunction "1_1") (pintype "passive"))
    )
    (net (code "72") (name "Net-(J4-2)") (class "Default")
      (node (ref "J4") (pin "TIP") (pinfunction "2_TIP") (pintype "passive"))
      (node (ref "R28") (pin "1") (pinfunction "1_1") (pintype "passive"))
    )
    (net (code "73") (name "Net-(J5-2)") (class "Default")
      (node (ref "J5") (pin "TIP") (pinfunction "2_TIP") (pintype "passive"))
      (node (ref "R34") (pin "1") (pinfunction "1_1") (pintype "passive"))
    )
    (net (code "74") (name "Net-(J5-3)") (class "Default")
      (node (ref "J5") (pin "SW") (pinfunction "3_SW") (pintype "passive"))
      (node (ref "R60") (pin "1") (pinfunction "1_1") (pintype "passive"))
    )
    (net (code "75") (name "Net-(J6-2)") (class "Default")
      (node (ref "J6") (pin "TIP") (pinfunction "2_TIP") (pintype "passive"))
      (node (ref "R61") (pin "2") (pinfunction "2_2") (pintype "passive"))
    )
    (net (code "76") (name "Net-(J7-2)") (class "Default")
      (node (ref "J7") (pin "TIP") (pinfunction "2_TIP") (pintype "passive"))
      (node (ref "R62") (pin "2") (pinfunction "2_2") (pintype "passive"))
    )
    (net (code "77") (name "Net-(J8-2)") (class "Default")
      (node (ref "J8") (pin "TIP") (pinfunction "2_TIP") (pintype "passive"))
      (node (ref "R35") (pin "1") (pinfunction "1_1") (pintype "passive"))
    )
    (net (code "78") (name "Net-(J8-3)") (class "Default")
      (node (ref "J8") (pin "SW") (pinfunction "3_SW") (pintype "passive"))
      (node (ref "R63") (pin "1") (pinfunction "1_1") (pintype "passive"))
    )
    (net (code "79") (name "Net-(JP6-Pad10)") (class "Default")
      (node (ref "JP6") (pin "10") (pinfunction "10_10") (pintype "passive"))
      (node (ref "JP6") (pin "9") (pinfunction "9_9") (pintype "passive"))
      (node (ref "P1") (pin "2") (pinfunction "2_2") (pintype "bidirectional"))
    )
    (net (code "80") (name "Net-(R27-A)") (class "Default")
      (node (ref "R27") (pin "P$3") (pinfunction "A_P$3") (pintype "passive"))
      (node (ref "R31") (pin "2") (pinfunction "2_2") (pintype "passive"))
    )
    (net (code "81") (name "Net-(R32-S)") (class "Default")
      (node (ref "R32") (pin "P$2") (pinfunction "S_P$2") (pintype "passive"))
      (node (ref "R34") (pin "2") (pinfunction "2_2") (pintype "passive"))
    )
    (net (code "82") (name "Net-(R33-S)") (class "Default")
      (node (ref "R33") (pin "P$2") (pinfunction "S_P$2") (pintype "passive"))
      (node (ref "R35") (pin "2") (pinfunction "2_2") (pintype "passive"))
    )
    (net (code "83") (name "Net-(R36-A)") (class "Default")
      (node (ref "R36") (pin "P$3") (pinfunction "A_P$3") (pintype "passive"))
      (node (ref "R45") (pin "2") (pinfunction "2_2") (pintype "passive"))
    )
    (net (code "84") (name "Net-(UC1-PA10{slash}USART1_RX{slash}TIM1_CH3)") (class "Default")
      (node (ref "R4") (pin "1") (pinfunction "1_1") (pintype "passive"))
      (node (ref "UC1") (pin "31") (pinfunction "PA10/USART1_RX/TIM1_CH3_31") (pintype "bidirectional"))
    )
    (net (code "85") (name "Net-(UC1-PA11{slash}USART1_CTS{slash}CAN_RX{slash}TIM1_CH4{slash}USBDM)") (class "Default")
      (node (ref "R5") (pin "1") (pinfunction "1_1") (pintype "passive"))
      (node (ref "UC1") (pin "32") (pinfunction "PA11/USART1_CTS/CAN_RX/TIM1_CH4/USBDM_32") (pintype "bidirectional"))
    )
    (net (code "86") (name "Net-(UC1-PD0-OSC_IN)") (class "Default")
      (node (ref "C5") (pin "2") (pinfunction "2_2") (pintype "passive"))
      (node (ref "Q1") (pin "2") (pinfunction "2_2") (pintype "passive"))
      (node (ref "UC1") (pin "5") (pinfunction "PD0-OSC_IN_5") (pintype "input"))
    )
    (net (code "87") (name "Net-(UC1-PD1-OSC_OUT)") (class "Default")
      (node (ref "C12") (pin "2") (pinfunction "2_2") (pintype "passive"))
      (node (ref "Q1") (pin "1") (pinfunction "1_1") (pintype "passive"))
      (node (ref "UC1") (pin "6") (pinfunction "PD1-OSC_OUT_6") (pintype "input"))
    )
    (net (code "88") (name "PWM_CUTOFF_1") (class "Default")
      (node (ref "C6") (pin "1") (pinfunction "1_1") (pintype "passive"))
      (node (ref "IC8") (pin "3") (pinfunction "CTRL_3") (pintype "input"))
      (node (ref "IC8") (pin "6") (pinfunction "CTRL_6") (pintype "input"))
      (node (ref "R4") (pin "2") (pinfunction "2_2") (pintype "passive"))
    )
    (net (code "89") (name "PWM_CUTOFF_2") (class "Default")
      (node (ref "C7") (pin "1") (pinfunction "1_1") (pintype "passive"))
      (node (ref "IC9") (pin "3") (pinfunction "CTRL_3") (pintype "input"))
      (node (ref "IC9") (pin "6") (pinfunction "CTRL_6") (pintype "input"))
      (node (ref "R5") (pin "2") (pinfunction "2_2") (pintype "passive"))
    )
    (net (code "90") (name "RESET") (class "Default")
      (node (ref "JP7") (pin "10") (pinfunction "10_10") (pintype "passive"))
      (node (ref "R1") (pin "1") (pinfunction "1_1") (pintype "passive"))
      (node (ref "UC1") (pin "7") (pinfunction "NRST_7") (pintype "input"))
    )
    (net (code "91") (name "SHAPE_1") (class "Default")
      (node (ref "R2") (pin "P$2") (pinfunction "S_P$2") (pintype "passive"))
      (node (ref "UC1") (pin "12") (pinfunction "PA2/USART2_TX/ADC12_IN2/TIM2_CH3_12") (pintype "bidirectional"))
    )
    (net (code "92") (name "SHAPE_2") (class "Default")
      (node (ref "R3") (pin "P$2") (pinfunction "S_P$2") (pintype "passive"))
      (node (ref "UC1") (pin "11") (pinfunction "PA1/USART2_RTS/ADC12_IN1/TIM2_CH2_11") (pintype "bidirectional"))
    )
    (net (code "93") (name "SW_METER") (class "Default")
      (node (ref "SW3") (pin "3") (pinfunction "3_3") (pintype "passive"))
      (node (ref "SW3") (pin "4") (pinfunction "4_4") (pintype "passive"))
      (node (ref "UC1") (pin "42") (pinfunction "PB6/I2C1_SCL/TIM4_CH1_42") (pintype "input"))
    )
    (net (code "94") (name "SW_MODE_1") (class "Default")
      (node (ref "SW1") (pin "3") (pinfunction "3_3") (pintype "passive"))
      (node (ref "SW1") (pin "4") (pinfunction "4_4") (pintype "passive"))
      (node (ref "UC1") (pin "41") (pinfunction "PB5/I2C1_SMBA_41") (pintype "input"))
    )
    (net (code "95") (name "SW_MODE_2") (class "Default")
      (node (ref "SW2") (pin "3") (pinfunction "3_3") (pintype "passive"))
      (node (ref "SW2") (pin "4") (pinfunction "4_4") (pintype "passive"))
      (node (ref "UC1") (pin "40") (pinfunction "PB4/NJTRST_40") (pintype "bidirectional"))
    )
    (net (code "96") (name "VCA_CONTROL_1") (class "Default")
      (node (ref "C30") (pin "2") (pinfunction "2_2") (pintype "passive"))
      (node (ref "D5") (pin "C") (pinfunction "C_C") (pintype "passive"))
      (node (ref "IC5") (pin "7") (pinfunction "OUT_7") (pintype "output"))
      (node (ref "IC8") (pin "14") (pinfunction "CTRL_14") (pintype "input"))
      (node (ref "R27") (pin "P$1") (pinfunction "E_P$1") (pintype "passive"))
      (node (ref "R6") (pin "2") (pinfunction "2_2") (pintype "passive"))
      (node (ref "TP1") (pin "P$1") (pinfunction "1_P$1") (pintype "bidirectional"))
    )
    (net (code "97") (name "VCA_CONTROL_2") (class "Default")
      (node (ref "C31") (pin "2") (pinfunction "2_2") (pintype "passive"))
      (node (ref "D4") (pin "C") (pinfunction "C_C") (pintype "passive"))
      (node (ref "IC6") (pin "7") (pinfunction "OUT_7") (pintype "output"))
      (node (ref "IC9") (pin "11") (pinfunction "CTRL_11") (pintype "input"))
      (node (ref "R36") (pin "P$1") (pinfunction "E_P$1") (pintype "passive"))
      (node (ref "R7") (pin "2") (pinfunction "2_2") (pintype "passive"))
      (node (ref "TP2") (pin "P$1") (pinfunction "1_P$1") (pintype "bidirectional"))
    )
    (net (code "98") (name "VCC") (class "Default")
      (node (ref "C24") (pin "+") (pinfunction "+_+") (pintype "passive"))
      (node (ref "C29") (pin "1") (pinfunction "1_1") (pintype "passive"))
      (node (ref "C32") (pin "1") (pinfunction "1_1") (pintype "passive"))
      (node (ref "C35") (pin "1") (pinfunction "1_1") (pintype "passive"))
      (node (ref "C41") (pin "1") (pinfunction "1_1") (pintype "passive"))
      (node (ref "C45") (pin "1") (pinfunction "1_1") (pintype "passive"))
      (node (ref "C46") (pin "1") (pinfunction "1_1") (pintype "passive"))
      (node (ref "D3") (pin "C") (pinfunction "C_C") (pintype "passive"))
      (node (ref "IC10") (pin "8") (pinfunction "V+_8") (pintype "power_in"))
      (node (ref "IC5") (pin "8") (pinfunction "V+_8") (pintype "power_in"))
      (node (ref "IC6") (pin "8") (pinfunction "V+_8") (pintype "power_in"))
      (node (ref "IC7") (pin "8") (pinfunction "V+_8") (pintype "power_in"))
      (node (ref "IC8") (pin "16") (pinfunction "V+_16") (pintype "power_in"))
      (node (ref "IC9") (pin "16") (pinfunction "V+_16") (pintype "power_in"))
      (node (ref "R11") (pin "1") (pinfunction "1_1") (pintype "passive"))
      (node (ref "R57") (pin "1") (pinfunction "1_1") (pintype "passive"))
    )
    (net (code "99") (name "VEE") (class "Default")
      (node (ref "C28") (pin "-") (pinfunction "-_-") (pintype "passive"))
      (node (ref "C33") (pin "2") (pinfunction "2_2") (pintype "passive"))
      (node (ref "C34") (pin "2") (pinfunction "2_2") (pintype "passive"))
      (node (ref "C39") (pin "2") (pinfunction "2_2") (pintype "passive"))
      (node (ref "C44") (pin "2") (pinfunction "2_2") (pintype "passive"))
      (node (ref "C48") (pin "2") (pinfunction "2_2") (pintype "passive"))
      (node (ref "C49") (pin "2") (pinfunction "2_2") (pintype "passive"))
      (node (ref "D6") (pin "A") (pinfunction "A_A") (pintype "passive"))
      (node (ref "IC10") (pin "4") (pinfunction "V-_4") (pintype "power_in"))
      (node (ref "IC5") (pin "4") (pinfunction "V-_4") (pintype "power_in"))
      (node (ref "IC6") (pin "4") (pinfunction "V-_4") (pintype "power_in"))
      (node (ref "IC7") (pin "4") (pinfunction "V-_4") (pintype "power_in"))
      (node (ref "IC8") (pin "9") (pinfunction "V-_9") (pintype "power_in"))
      (node (ref "IC9") (pin "9") (pinfunction "V-_9") (pintype "power_in"))
      (node (ref "P1") (pin "1") (pinfunction "1_1") (pintype "bidirectional"))
      (node (ref "R46") (pin "1") (pinfunction "1_1") (pintype "passive"))
    )
    (net (code "100") (name "unconnected-(IC8E-MODE-Pad1)") (class "Default")
      (node (ref "IC8") (pin "1") (pinfunction "MODE_1") (pintype "input"))
    )
    (net (code "101") (name "unconnected-(IC9E-MODE-Pad1)") (class "Default")
      (node (ref "IC9") (pin "1") (pinfunction "MODE_1") (pintype "input"))
    )
    (net (code "102") (name "unconnected-(J1-3-PadSW)") (class "Default")
      (node (ref "J1") (pin "SW") (pinfunction "3_SW") (pintype "passive"))
    )
    (net (code "103") (name "unconnected-(J4-3-PadSW)") (class "Default")
      (node (ref "J4") (pin "SW") (pinfunction "3_SW") (pintype "passive"))
    )
    (net (code "104") (name "unconnected-(J6-3-PadSW)") (class "Default")
      (node (ref "J6") (pin "SW") (pinfunction "3_SW") (pintype "passive"))
    )
    (net (code "105") (name "unconnected-(J7-3-PadSW)") (class "Default")
      (node (ref "J7") (pin "SW") (pinfunction "3_SW") (pintype "passive"))
    )
    (net (code "106") (name "unconnected-(JP7-Pad7)") (class "Default")
      (node (ref "JP7") (pin "7") (pinfunction "7_7") (pintype "passive"))
    )
    (net (code "107") (name "unconnected-(UC1-PA8{slash}USART1_CK{slash}TIM1_CH1{slash}MCO-Pad29)") (class "Default")
      (node (ref "UC1") (pin "29") (pinfunction "PA8/USART1_CK/TIM1_CH1/MCO_29") (pintype "bidirectional"))
    )
    (net (code "108") (name "unconnected-(UC1-PA9{slash}USART1_TX{slash}TIM1_CH2-Pad30)") (class "Default")
      (node (ref "UC1") (pin "30") (pinfunction "PA9/USART1_TX/TIM1_CH2_30") (pintype "input"))
    )
    (net (code "109") (name "unconnected-(UC1-PA12{slash}USART1_RTS{slash}CAN_TX{slash}TIM1_ETR{slash}USBDP-Pad33)") (class "Default")
      (node (ref "UC1") (pin "33") (pinfunction "PA12/USART1_RTS/CAN_TX/TIM1_ETR/USBDP_33") (pintype "bidirectional"))
    )
    (net (code "110") (name "unconnected-(UC1-PB8{slash}TIM4_CH3-Pad45)") (class "Default")
      (node (ref "UC1") (pin "45") (pinfunction "PB8/TIM4_CH3_45") (pintype "bidirectional"))
    )
    (net (code "111") (name "unconnected-(UC1-PB9{slash}TIM4_CH4-Pad46)") (class "Default")
      (node (ref "UC1") (pin "46") (pinfunction "PB9/TIM4_CH4_46") (pintype "input"))
    )
    (net (code "112") (name "unconnected-(UC1-PB14{slash}SPI2_MISO{slash}USART3_RTS{slash}TIM1_CH2N-Pad27)") (class "Default")
      (node (ref "UC1") (pin "27") (pinfunction "PB14/SPI2_MISO/USART3_RTS/TIM1_CH2N_27") (pintype "input"))
    )
    (net (code "113") (name "unconnected-(UC1-PC13-TAMPER-RTC-Pad2)") (class "Default")
      (node (ref "UC1") (pin "2") (pinfunction "PC13-TAMPER-RTC_2") (pintype "input"))
    )
    (net (code "114") (name "unconnected-(UC1-PC14-OSC32_IN-Pad3)") (class "Default")
      (node (ref "UC1") (pin "3") (pinfunction "PC14-OSC32_IN_3") (pintype "input"))
    )
    (net (code "115") (name "unconnected-(UC1-PC15-OSC32_OUT-Pad4)") (class "Default")
      (node (ref "UC1") (pin "4") (pinfunction "PC15-OSC32_OUT_4") (pintype "input"))
    )
  )
)
